# P1R5.net
KiCad netlist of a schematic drawn in EAGLE
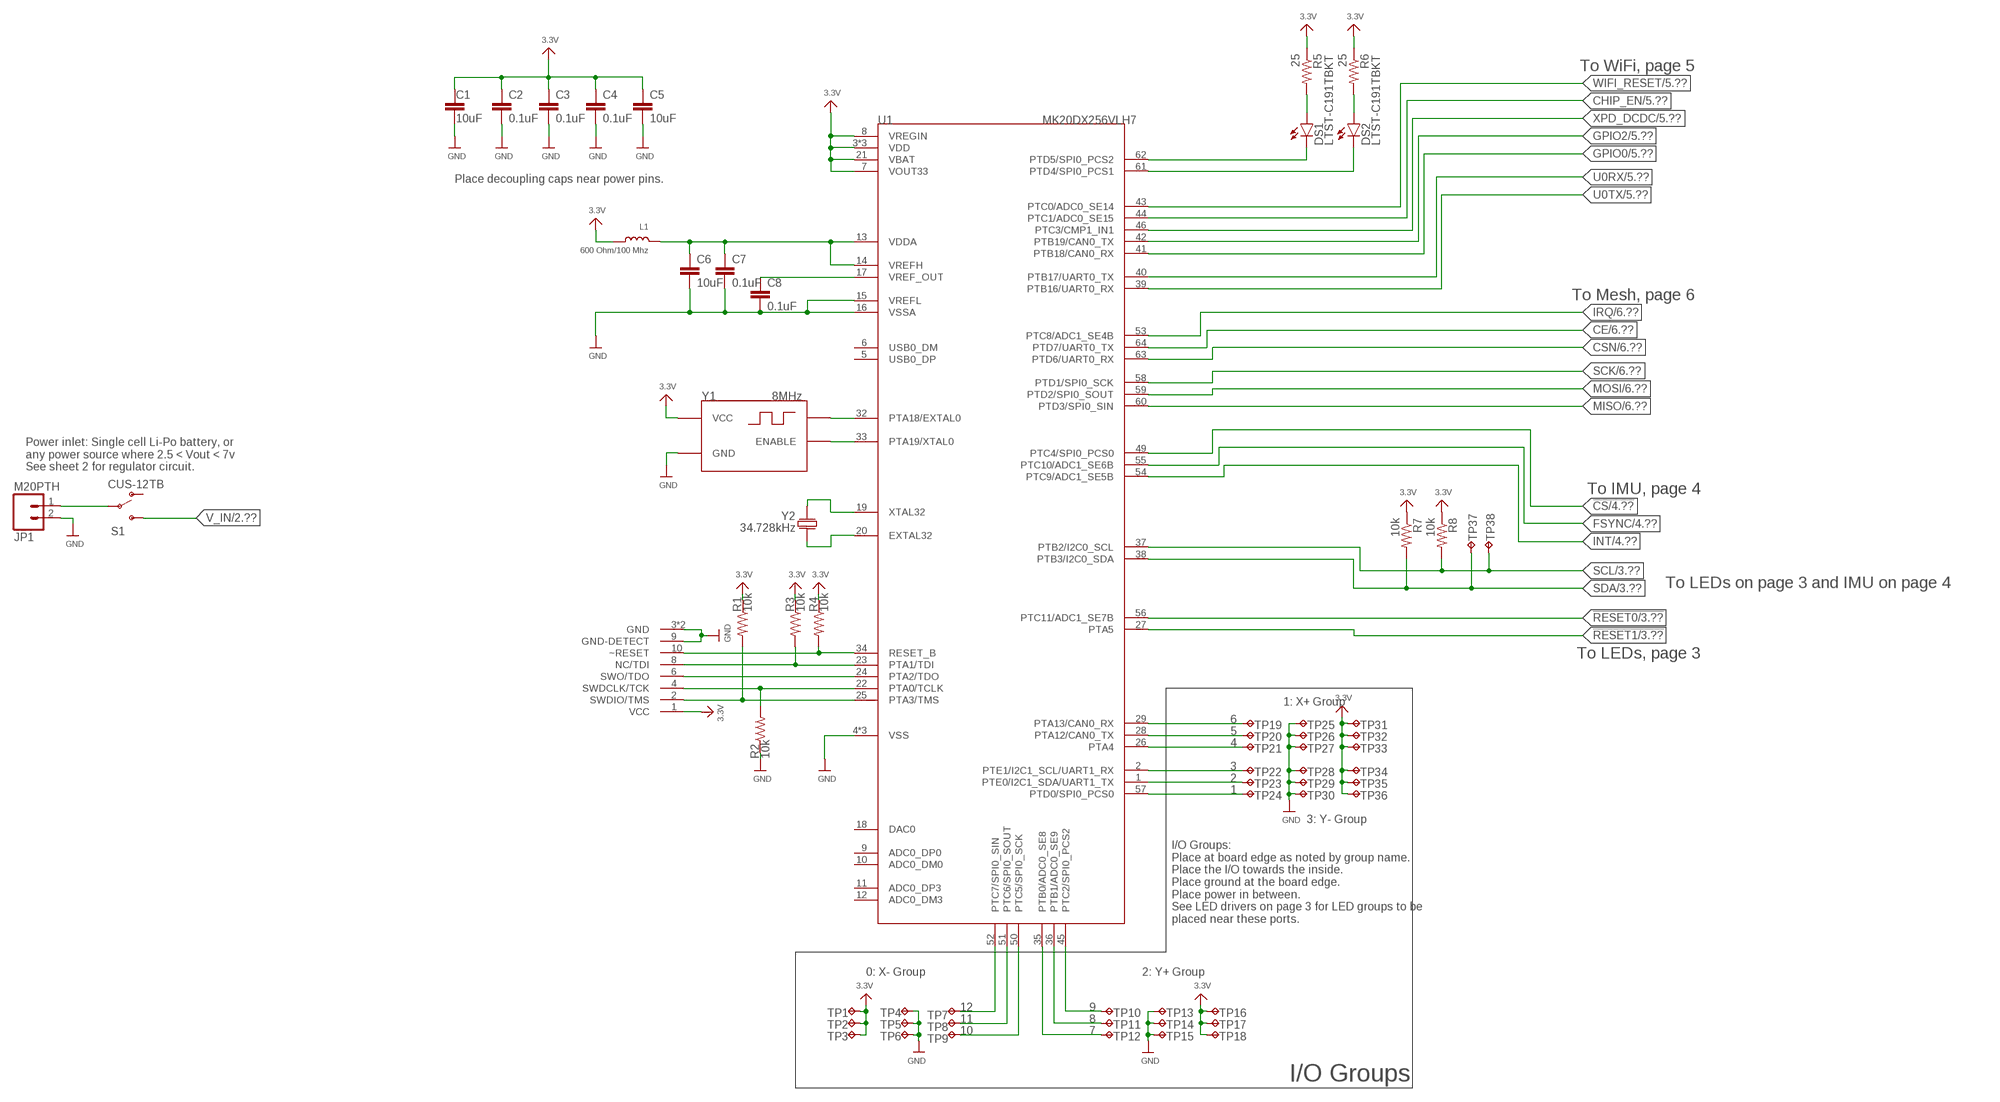
[diagram p0: schematic, sheet 1]
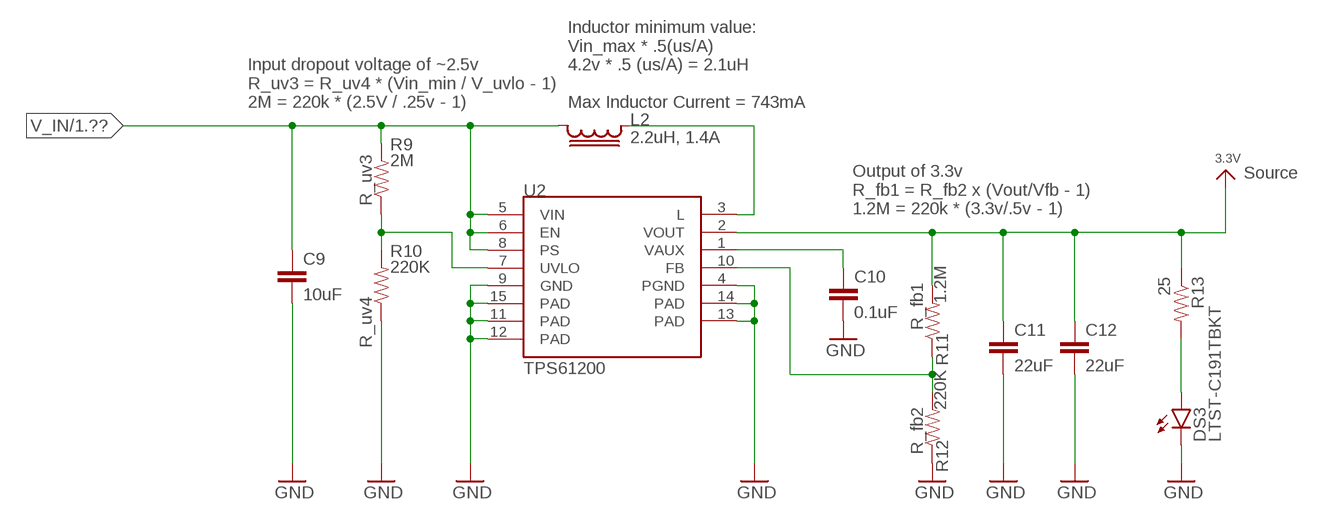
[diagram p1: schematic, sheet 2]
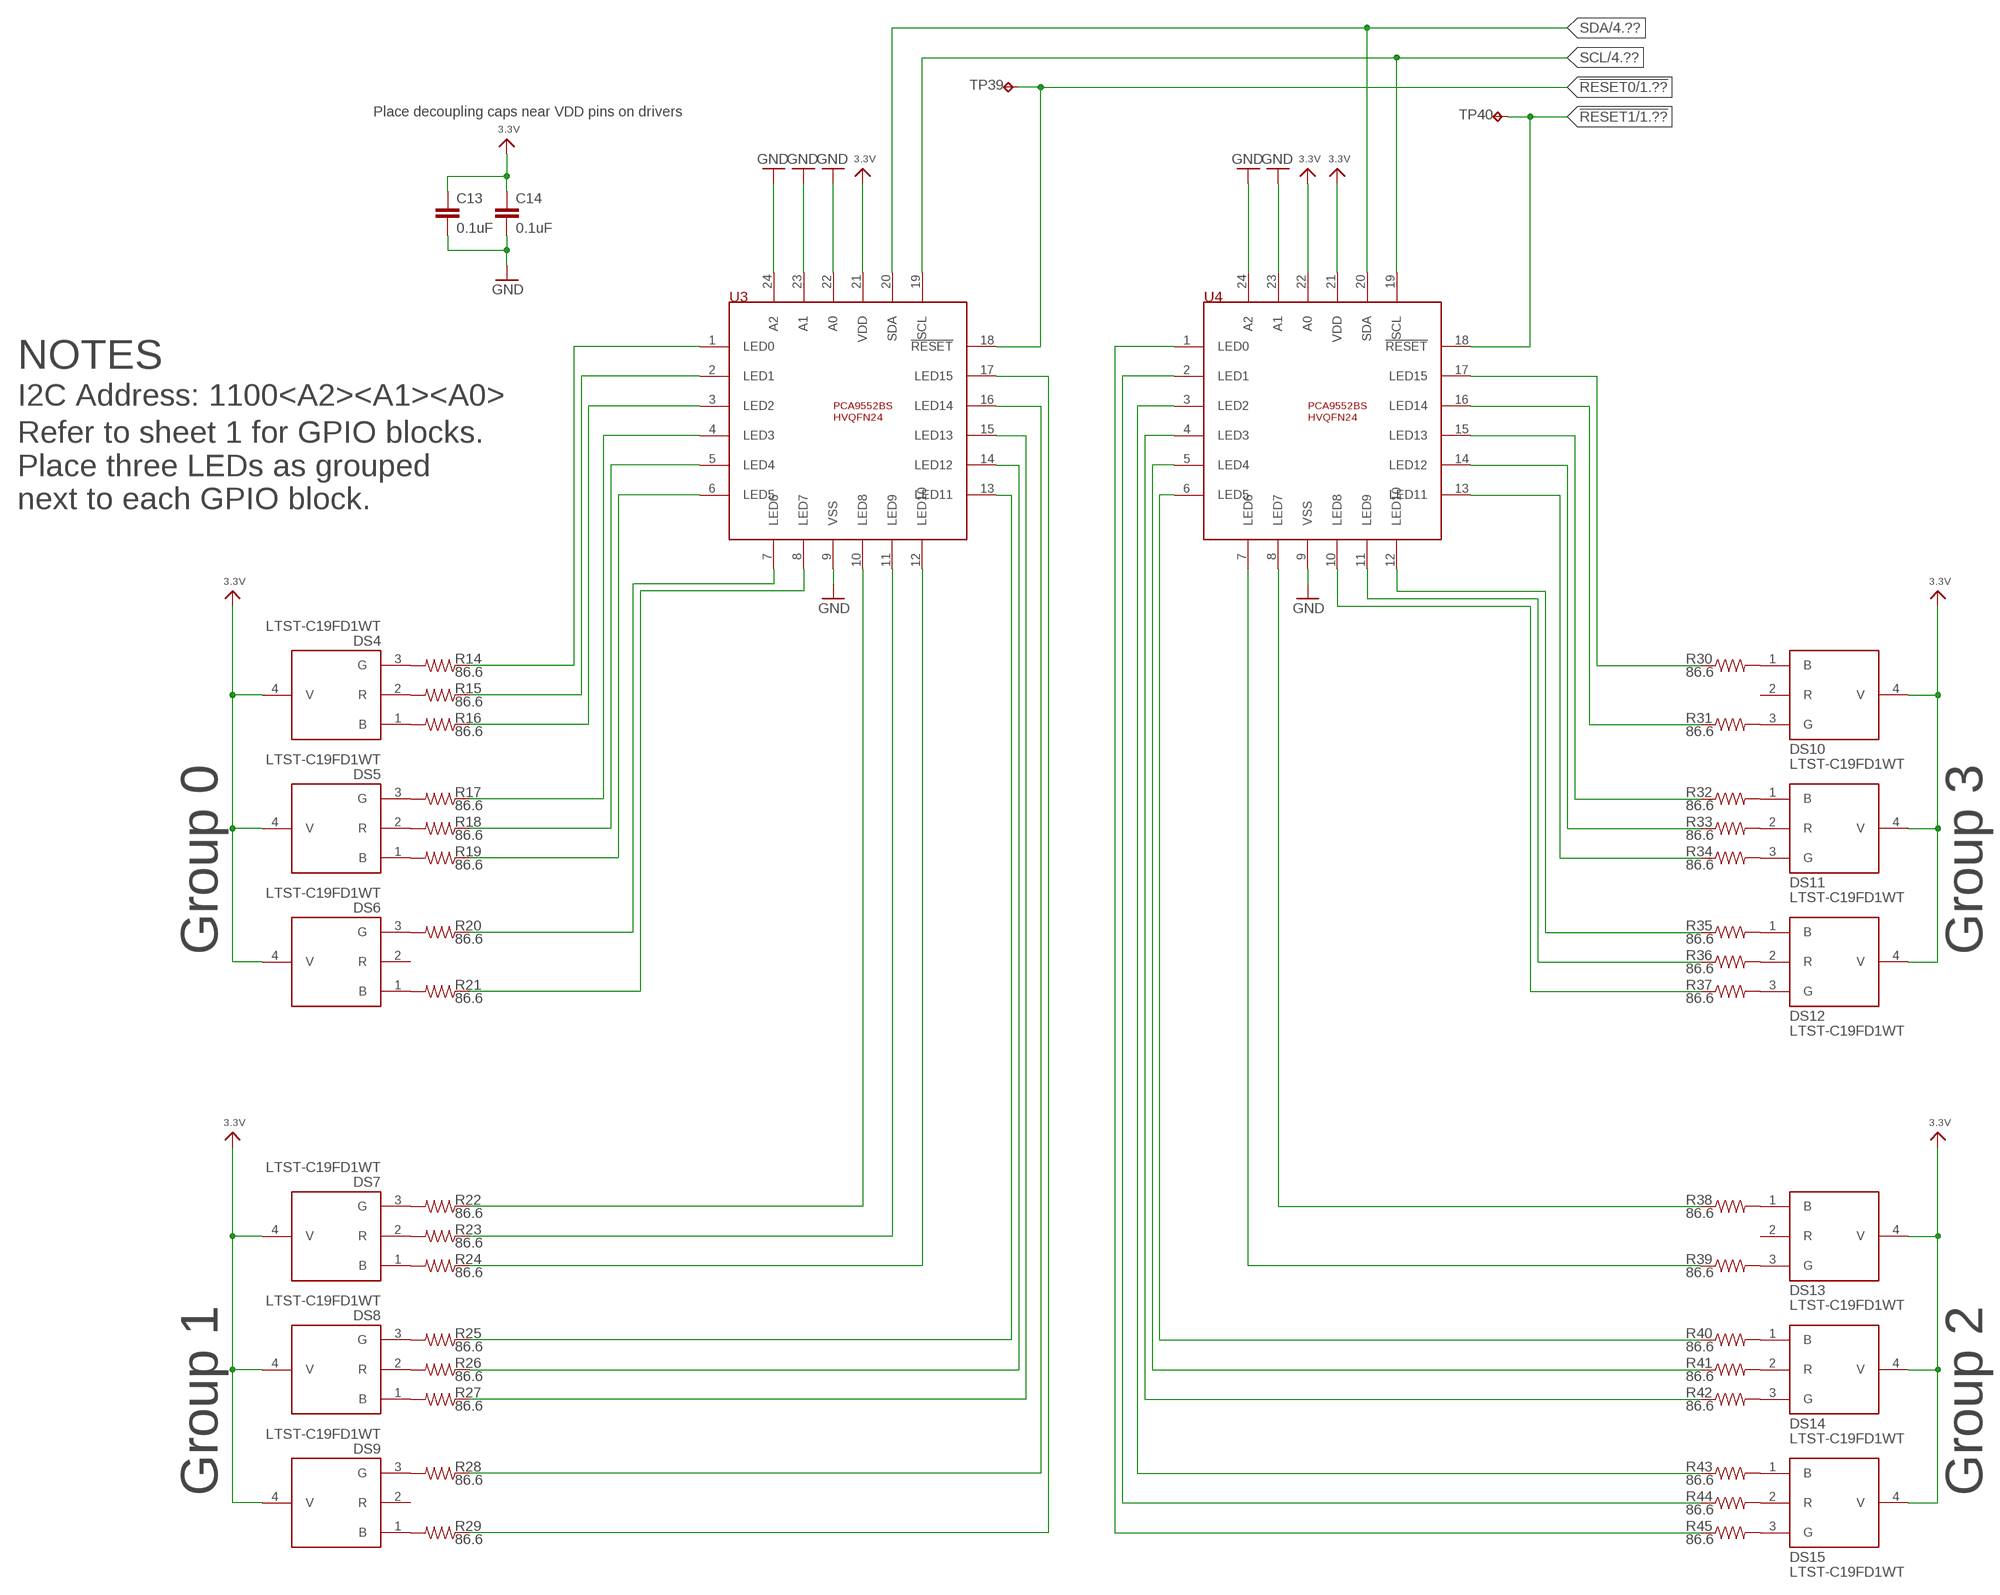
[diagram p2: schematic, sheet 3]
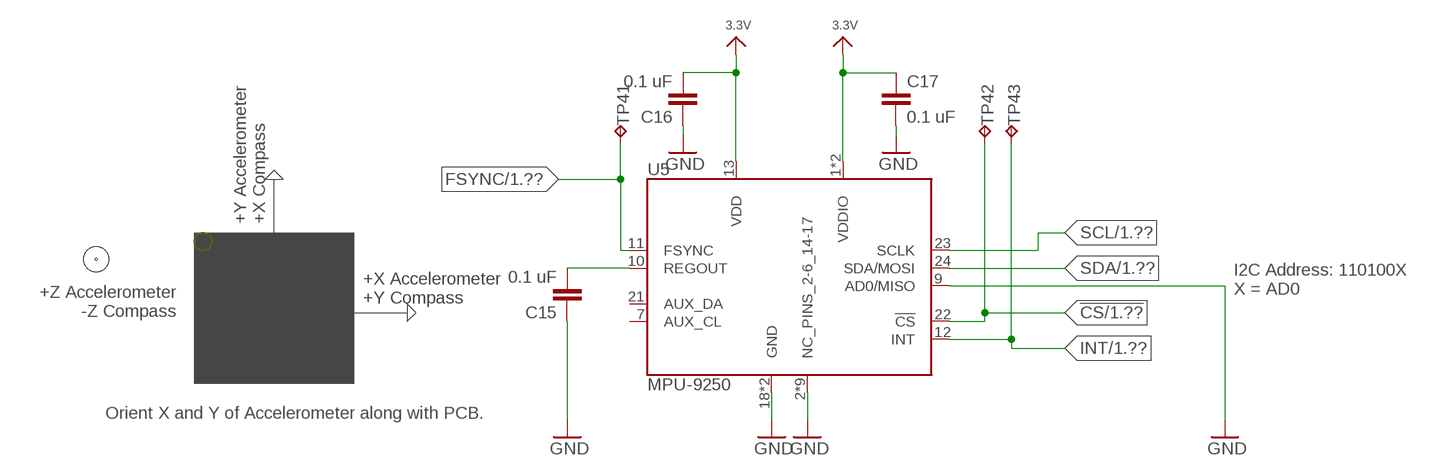
[diagram p3: schematic, sheet 4]
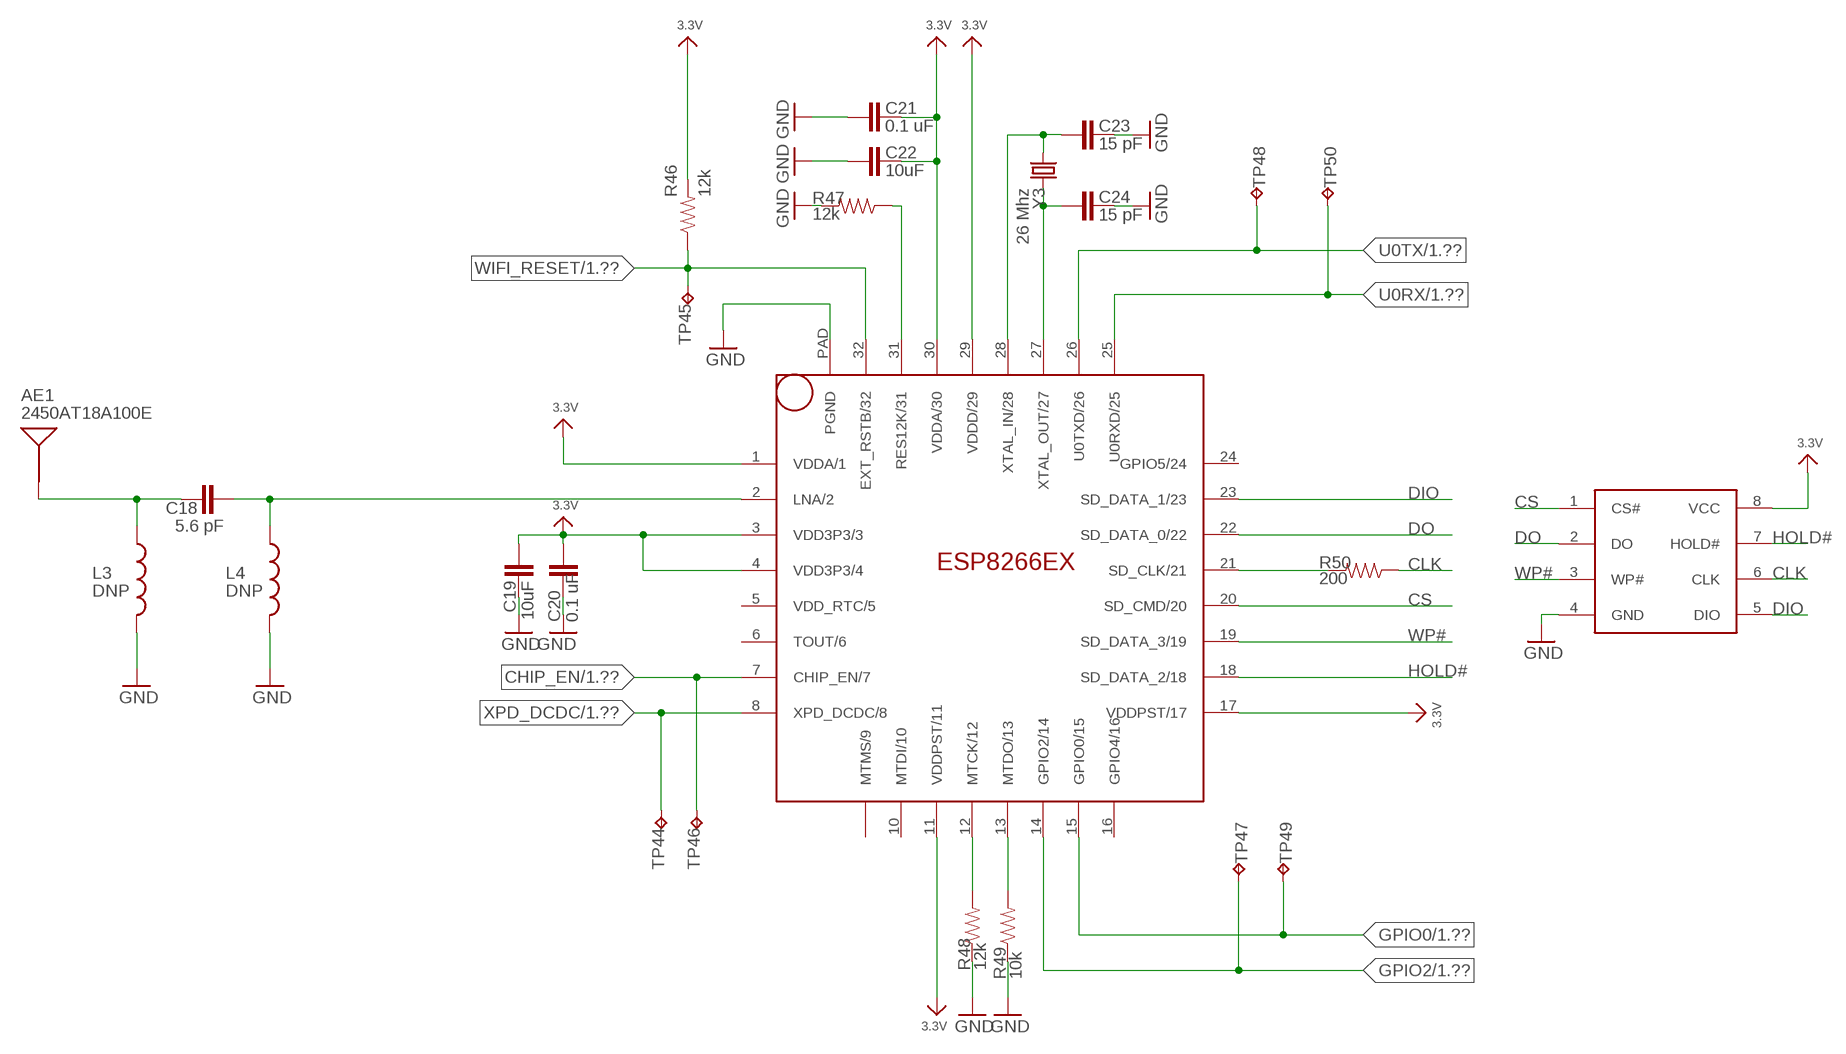
[diagram p4: schematic, sheet 5]
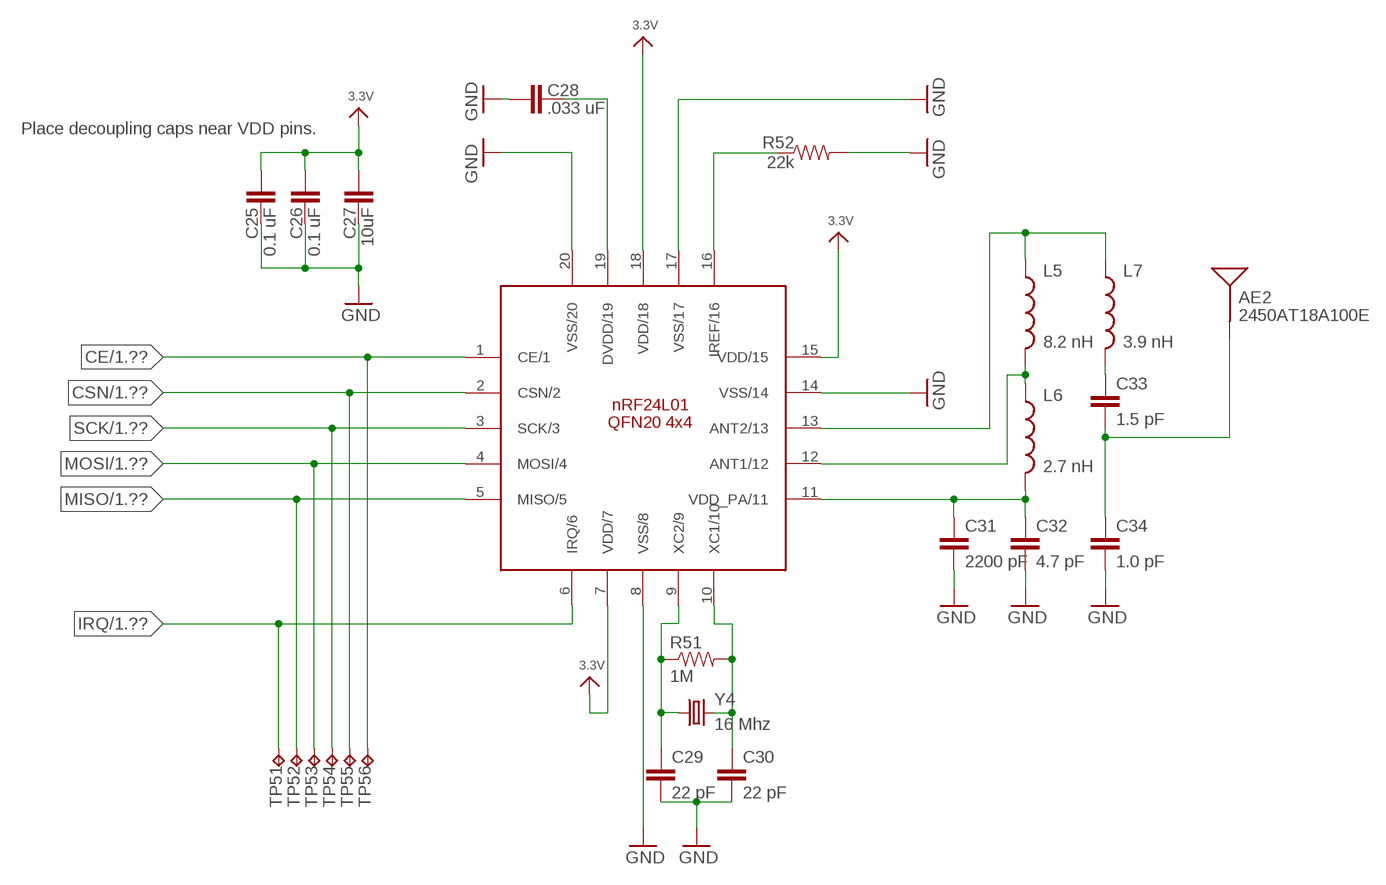
[diagram p5: schematic, sheet 6]

(export (version "E")
  (design (tool "Eeschema 10.0.6"))
  (components
    (comp (ref "C9")
      (value "10uF")
      (footprint "eagle-import:0603-CAP")
      (fields (field (name "PARTNO") "C1608X7S0J106M080AC"))
      (libsource (lib "eagle-import") (part "CAP0603-CAP"))
    )
    (comp (ref "C10")
      (value "0.1uF")
      (footprint "eagle-import:0402-CAP")
      (fields (field (name "PARTNO") "C1005X7R1C104K050BC"))
      (libsource (lib "eagle-import") (part "CAP0402-CAP"))
    )
    (comp (ref "C11")
      (value "22uF")
      (footprint "eagle-import:1210")
      (fields (field (name "PARTNO") "C3225X7R1A226K230AC"))
      (libsource (lib "eagle-import") (part "CAP1210"))
    )
    (comp (ref "C12")
      (value "22uF")
      (footprint "eagle-import:1210")
      (fields (field (name "PARTNO") "C3225X7R1A226K230AC"))
      (libsource (lib "eagle-import") (part "CAP1210"))
    )
    (comp (ref "DS3")
      (value "LTST-C191TBKT")
      (footprint "eagle-import:LED-0603")
      (fields (field (name "MF") "Avago") (field (name "MPN") "HSMG-C190"))
      (libsource (lib "eagle-import") (part "LED-GREEN"))
    )
    (comp (ref "L2")
      (value "2.2uH, 1.4A")
      (footprint "eagle-import:LPS3015")
      (fields
        (field (name "MF") "Coilcraft")
        (field (name "MPN") "LPS3015-222MRB")
        (field (name "PARTNO") "BRL3225T2R2M")
      )
      (libsource (lib "eagle-import") (part "LPS30152.2UH"))
    )
    (comp (ref "R9")
      (value "2M")
      (footprint "eagle-import:_0402")
      (fields (field (name "PARTNO") "CRCW04022M00FKED"))
      (libsource (lib "eagle-import") (part "RESISTOR0402"))
    )
    (comp (ref "R10")
      (value "220K")
      (footprint "eagle-import:_0402")
      (fields (field (name "PARTNO") "CRCW0402220KFKED"))
      (libsource (lib "eagle-import") (part "RESISTOR0402"))
    )
    (comp (ref "R11")
      (value "1.2M")
      (footprint "eagle-import:_0402")
      (fields (field (name "PARTNO") "CRCW04021M20FKED"))
      (libsource (lib "eagle-import") (part "RESISTOR0402"))
    )
    (comp (ref "R12")
      (value "220K")
      (footprint "eagle-import:_0402")
      (fields (field (name "PARTNO") "CRCW0402220KFKED"))
      (libsource (lib "eagle-import") (part "RESISTOR0402"))
    )
    (comp (ref "R13")
      (value "25")
      (footprint "eagle-import:_0402")
      (fields (field (name "PARTNO") "CRCW040224R9FKED"))
      (libsource (lib "eagle-import") (part "RESISTOR0402"))
    )
    (comp (ref "U2")
      (value "TPS61200")
      (footprint "eagle-import:QFN-10_PAD")
      (fields (field (name "MF") "Texas Instruments") (field (name "MPN") "TPS61200DRCR"))
      (libsource (lib "eagle-import") (part "TPS61200"))
    )
    (comp (ref "C13")
      (value "0.1uF")
      (footprint "eagle-import:0402-CAP")
      (fields (field (name "PARTNO") "C1005X7R1C104K050BC"))
      (libsource (lib "eagle-import") (part "CAP0402-CAP"))
    )
    (comp (ref "C14")
      (value "0.1uF")
      (footprint "eagle-import:0402-CAP")
      (fields (field (name "PARTNO") "C1005X7R1C104K050BC"))
      (libsource (lib "eagle-import") (part "CAP0402-CAP"))
    )
    (comp (ref "DS4")
      (value "LTST-C19FD1WT")
      (footprint "eagle-import:LTST-C19FD1WT")
      (libsource (lib "eagle-import") (part "LTST-C19FD1WT"))
    )
    (comp (ref "DS5")
      (value "LTST-C19FD1WT")
      (footprint "eagle-import:LTST-C19FD1WT")
      (libsource (lib "eagle-import") (part "LTST-C19FD1WT"))
    )
    (comp (ref "DS6")
      (value "LTST-C19FD1WT")
      (footprint "eagle-import:LTST-C19FD1WT")
      (libsource (lib "eagle-import") (part "LTST-C19FD1WT"))
    )
    (comp (ref "DS7")
      (value "LTST-C19FD1WT")
      (footprint "eagle-import:LTST-C19FD1WT")
      (libsource (lib "eagle-import") (part "LTST-C19FD1WT"))
    )
    (comp (ref "DS8")
      (value "LTST-C19FD1WT")
      (footprint "eagle-import:LTST-C19FD1WT")
      (libsource (lib "eagle-import") (part "LTST-C19FD1WT"))
    )
    (comp (ref "DS9")
      (value "LTST-C19FD1WT")
      (footprint "eagle-import:LTST-C19FD1WT")
      (libsource (lib "eagle-import") (part "LTST-C19FD1WT"))
    )
    (comp (ref "DS10")
      (value "LTST-C19FD1WT")
      (footprint "eagle-import:LTST-C19FD1WT")
      (libsource (lib "eagle-import") (part "LTST-C19FD1WT"))
    )
    (comp (ref "DS11")
      (value "LTST-C19FD1WT")
      (footprint "eagle-import:LTST-C19FD1WT")
      (libsource (lib "eagle-import") (part "LTST-C19FD1WT"))
    )
    (comp (ref "DS12")
      (value "LTST-C19FD1WT")
      (footprint "eagle-import:LTST-C19FD1WT")
      (libsource (lib "eagle-import") (part "LTST-C19FD1WT"))
    )
    (comp (ref "DS13")
      (value "LTST-C19FD1WT")
      (footprint "eagle-import:LTST-C19FD1WT")
      (libsource (lib "eagle-import") (part "LTST-C19FD1WT"))
    )
    (comp (ref "DS14")
      (value "LTST-C19FD1WT")
      (footprint "eagle-import:LTST-C19FD1WT")
      (libsource (lib "eagle-import") (part "LTST-C19FD1WT"))
    )
    (comp (ref "DS15")
      (value "LTST-C19FD1WT")
      (footprint "eagle-import:LTST-C19FD1WT")
      (libsource (lib "eagle-import") (part "LTST-C19FD1WT"))
    )
    (comp (ref "R14")
      (value "86.6")
      (footprint "eagle-import:_0402")
      (fields (field (name "PARTNO") "5-1879213-0"))
      (libsource (lib "eagle-import") (part "RESISTOR0402"))
    )
    (comp (ref "R15")
      (value "86.6")
      (footprint "eagle-import:_0402")
      (fields (field (name "PARTNO") "5-1879213-0"))
      (libsource (lib "eagle-import") (part "RESISTOR0402"))
    )
    (comp (ref "R16")
      (value "86.6")
      (footprint "eagle-import:_0402")
      (fields (field (name "PARTNO") "5-1879213-0"))
      (libsource (lib "eagle-import") (part "RESISTOR0402"))
    )
    (comp (ref "R17")
      (value "86.6")
      (footprint "eagle-import:_0402")
      (fields (field (name "PARTNO") "5-1879213-0"))
      (libsource (lib "eagle-import") (part "RESISTOR0402"))
    )
    (comp (ref "R18")
      (value "86.6")
      (footprint "eagle-import:_0402")
      (fields (field (name "PARTNO") "5-1879213-0"))
      (libsource (lib "eagle-import") (part "RESISTOR0402"))
    )
    (comp (ref "R19")
      (value "86.6")
      (footprint "eagle-import:_0402")
      (fields (field (name "PARTNO") "5-1879213-0"))
      (libsource (lib "eagle-import") (part "RESISTOR0402"))
    )
    (comp (ref "R20")
      (value "86.6")
      (footprint "eagle-import:_0402")
      (fields (field (name "PARTNO") "5-1879213-0"))
      (libsource (lib "eagle-import") (part "RESISTOR0402"))
    )
    (comp (ref "R21")
      (value "86.6")
      (footprint "eagle-import:_0402")
      (fields (field (name "PARTNO") "5-1879213-0"))
      (libsource (lib "eagle-import") (part "RESISTOR0402"))
    )
    (comp (ref "R22")
      (value "86.6")
      (footprint "eagle-import:_0402")
      (fields (field (name "PARTNO") "5-1879213-0"))
      (libsource (lib "eagle-import") (part "RESISTOR0402"))
    )
    (comp (ref "R23")
      (value "86.6")
      (footprint "eagle-import:_0402")
      (fields (field (name "PARTNO") "5-1879213-0"))
      (libsource (lib "eagle-import") (part "RESISTOR0402"))
    )
    (comp (ref "R24")
      (value "86.6")
      (footprint "eagle-import:_0402")
      (fields (field (name "PARTNO") "5-1879213-0"))
      (libsource (lib "eagle-import") (part "RESISTOR0402"))
    )
    (comp (ref "R25")
      (value "86.6")
      (footprint "eagle-import:_0402")
      (fields (field (name "PARTNO") "5-1879213-0"))
      (libsource (lib "eagle-import") (part "RESISTOR0402"))
    )
    (comp (ref "R26")
      (value "86.6")
      (footprint "eagle-import:_0402")
      (fields (field (name "PARTNO") "5-1879213-0"))
      (libsource (lib "eagle-import") (part "RESISTOR0402"))
    )
    (comp (ref "R27")
      (value "86.6")
      (footprint "eagle-import:_0402")
      (fields (field (name "PARTNO") "5-1879213-0"))
      (libsource (lib "eagle-import") (part "RESISTOR0402"))
    )
    (comp (ref "R28")
      (value "86.6")
      (footprint "eagle-import:_0402")
      (fields (field (name "PARTNO") "5-1879213-0"))
      (libsource (lib "eagle-import") (part "RESISTOR0402"))
    )
    (comp (ref "R29")
      (value "86.6")
      (footprint "eagle-import:_0402")
      (fields (field (name "PARTNO") "5-1879213-0"))
      (libsource (lib "eagle-import") (part "RESISTOR0402"))
    )
    (comp (ref "R30")
      (value "86.6")
      (footprint "eagle-import:_0402")
      (fields (field (name "PARTNO") "5-1879213-0"))
      (libsource (lib "eagle-import") (part "RESISTOR0402"))
    )
    (comp (ref "R31")
      (value "86.6")
      (footprint "eagle-import:_0402")
      (fields (field (name "PARTNO") "5-1879213-0"))
      (libsource (lib "eagle-import") (part "RESISTOR0402"))
    )
    (comp (ref "R32")
      (value "86.6")
      (footprint "eagle-import:_0402")
      (fields (field (name "PARTNO") "5-1879213-0"))
      (libsource (lib "eagle-import") (part "RESISTOR0402"))
    )
    (comp (ref "R33")
      (value "86.6")
      (footprint "eagle-import:_0402")
      (fields (field (name "PARTNO") "5-1879213-0"))
      (libsource (lib "eagle-import") (part "RESISTOR0402"))
    )
    (comp (ref "R34")
      (value "86.6")
      (footprint "eagle-import:_0402")
      (fields (field (name "PARTNO") "5-1879213-0"))
      (libsource (lib "eagle-import") (part "RESISTOR0402"))
    )
    (comp (ref "R35")
      (value "86.6")
      (footprint "eagle-import:_0402")
      (fields (field (name "PARTNO") "5-1879213-0"))
      (libsource (lib "eagle-import") (part "RESISTOR0402"))
    )
    (comp (ref "R36")
      (value "86.6")
      (footprint "eagle-import:_0402")
      (fields (field (name "PARTNO") "5-1879213-0"))
      (libsource (lib "eagle-import") (part "RESISTOR0402"))
    )
    (comp (ref "R37")
      (value "86.6")
      (footprint "eagle-import:_0402")
      (fields (field (name "PARTNO") "5-1879213-0"))
      (libsource (lib "eagle-import") (part "RESISTOR0402"))
    )
    (comp (ref "R38")
      (value "86.6")
      (footprint "eagle-import:_0402")
      (fields (field (name "PARTNO") "5-1879213-0"))
      (libsource (lib "eagle-import") (part "RESISTOR0402"))
    )
    (comp (ref "R39")
      (value "86.6")
      (footprint "eagle-import:_0402")
      (fields (field (name "PARTNO") "5-1879213-0"))
      (libsource (lib "eagle-import") (part "RESISTOR0402"))
    )
    (comp (ref "R40")
      (value "86.6")
      (footprint "eagle-import:_0402")
      (fields (field (name "PARTNO") "5-1879213-0"))
      (libsource (lib "eagle-import") (part "RESISTOR0402"))
    )
    (comp (ref "R41")
      (value "86.6")
      (footprint "eagle-import:_0402")
      (fields (field (name "PARTNO") "5-1879213-0"))
      (libsource (lib "eagle-import") (part "RESISTOR0402"))
    )
    (comp (ref "R42")
      (value "86.6")
      (footprint "eagle-import:_0402")
      (fields (field (name "PARTNO") "5-1879213-0"))
      (libsource (lib "eagle-import") (part "RESISTOR0402"))
    )
    (comp (ref "R43")
      (value "86.6")
      (footprint "eagle-import:_0402")
      (fields (field (name "PARTNO") "5-1879213-0"))
      (libsource (lib "eagle-import") (part "RESISTOR0402"))
    )
    (comp (ref "R44")
      (value "86.6")
      (footprint "eagle-import:_0402")
      (fields (field (name "PARTNO") "5-1879213-0"))
      (libsource (lib "eagle-import") (part "RESISTOR0402"))
    )
    (comp (ref "R45")
      (value "86.6")
      (footprint "eagle-import:_0402")
      (fields (field (name "PARTNO") "5-1879213-0"))
      (libsource (lib "eagle-import") (part "RESISTOR0402"))
    )
    (comp (ref "TP39")
      (value "TPTP08R")
      (footprint "eagle-import:TP08R")
      (fields (field (name "PARTNO") "TEST POINT"))
      (libsource (lib "eagle-import") (part "TPTP08R"))
    )
    (comp (ref "TP40")
      (value "TPTP08R")
      (footprint "eagle-import:TP08R")
      (fields (field (name "PARTNO") "TEST POINT"))
      (libsource (lib "eagle-import") (part "TPTP08R"))
    )
    (comp (ref "U3")
      (value "PCA9552BS")
      (footprint "eagle-import:HVQFN24")
      (libsource (lib "eagle-import") (part "PCA9552BS"))
    )
    (comp (ref "U4")
      (value "PCA9552BS")
      (footprint "eagle-import:HVQFN24")
      (libsource (lib "eagle-import") (part "PCA9552BS"))
    )
    (comp (ref "AE2")
      (value "2450AT18A100E")
      (footprint "eagle-import:ANTENNA-CHIP2")
      (libsource (lib "eagle-import") (part "ANTENNA2SMD"))
    )
    (comp (ref "C25")
      (value "0.1 uF")
      (footprint "eagle-import:0402-CAP")
      (fields (field (name "PARTNO") "C1005X7R1C104K050BC"))
      (libsource (lib "eagle-import") (part "CAP0402-CAP"))
    )
    (comp (ref "C26")
      (value "0.1 uF")
      (footprint "eagle-import:0402-CAP")
      (fields (field (name "PARTNO") "C1005X7R1C104K050BC"))
      (libsource (lib "eagle-import") (part "CAP0402-CAP"))
    )
    (comp (ref "C27")
      (value "10uF")
      (footprint "eagle-import:0603-CAP")
      (fields (field (name "PARTNO") "C1608X7S0J106M080AC"))
      (libsource (lib "eagle-import") (part "CAP0603-CAP"))
    )
    (comp (ref "C28")
      (value ".033 uF")
      (footprint "eagle-import:0402-CAP")
      (fields (field (name "PARTNO") "C1005X7R1H333K050BB"))
      (libsource (lib "eagle-import") (part "CAP0402-CAP"))
    )
    (comp (ref "C29")
      (value "22 pF")
      (footprint "eagle-import:0402-CAP")
      (fields (field (name "PARTNO") "C1005C0G1H220J050BA"))
      (libsource (lib "eagle-import") (part "CAP0402-CAP"))
    )
    (comp (ref "C30")
      (value "22 pF")
      (footprint "eagle-import:0402-CAP")
      (fields (field (name "PARTNO") "C1005C0G1H220J050BA"))
      (libsource (lib "eagle-import") (part "CAP0402-CAP"))
    )
    (comp (ref "C31")
      (value "2200 pF")
      (footprint "eagle-import:0402-CAP")
      (fields (field (name "PARTNO") "C1005X7R1H222K050BA"))
      (libsource (lib "eagle-import") (part "CAP0402-CAP"))
    )
    (comp (ref "C32")
      (value "4.7 pF")
      (footprint "eagle-import:0402-CAP")
      (fields (field (name "PARTNO") "CGA2B2C0G1H4R7C050BA"))
      (libsource (lib "eagle-import") (part "CAP0402-CAP"))
    )
    (comp (ref "C33")
      (value "1.5 pF")
      (footprint "eagle-import:0402-CAP")
      (fields (field (name "PARTNO") "C1005C0G1H1R5B050BA"))
      (libsource (lib "eagle-import") (part "CAP0402-CAP"))
    )
    (comp (ref "C34")
      (value "1.0 pF")
      (footprint "eagle-import:0402-CAP")
      (fields (field (name "PARTNO") "C1005C0G1H010B050BA"))
      (libsource (lib "eagle-import") (part "CAP0402-CAP"))
    )
    (comp (ref "L5")
      (value "8.2 nH")
      (footprint "eagle-import:C0402")
      (fields (field (name "PARTNO") "L-07C8N2JV6T"))
      (libsource (lib "eagle-import") (part "INDUCTOR0402"))
    )
    (comp (ref "L6")
      (value "2.7 nH")
      (footprint "eagle-import:C0402")
      (fields (field (name "PARTNO") "L-07C2N7SV6T"))
      (libsource (lib "eagle-import") (part "INDUCTOR0402"))
    )
    (comp (ref "L7")
      (value "3.9 nH")
      (footprint "eagle-import:C0402")
      (fields (field (name "PARTNO") "L-07C3N9SV6T"))
      (libsource (lib "eagle-import") (part "INDUCTOR0402"))
    )
    (comp (ref "R51")
      (value "1M")
      (footprint "eagle-import:_0402")
      (fields (field (name "PARTNO") "CRCW04021M00FKED"))
      (libsource (lib "eagle-import") (part "RESISTOR0402"))
    )
    (comp (ref "R52")
      (value "22k")
      (footprint "eagle-import:_0402")
      (fields (field (name "PARTNO") "CRCW040222K0FKED"))
      (libsource (lib "eagle-import") (part "RESISTOR0402"))
    )
    (comp (ref "TP51")
      (value "TPTP08R")
      (footprint "eagle-import:TP08R")
      (fields (field (name "PARTNO") "TEST POINT"))
      (libsource (lib "eagle-import") (part "TPTP08R"))
    )
    (comp (ref "TP52")
      (value "TPTP08R")
      (footprint "eagle-import:TP08R")
      (fields (field (name "PARTNO") "TEST POINT"))
      (libsource (lib "eagle-import") (part "TPTP08R"))
    )
    (comp (ref "TP53")
      (value "TPTP08R")
      (footprint "eagle-import:TP08R")
      (fields (field (name "PARTNO") "TEST POINT"))
      (libsource (lib "eagle-import") (part "TPTP08R"))
    )
    (comp (ref "TP54")
      (value "TPTP08R")
      (footprint "eagle-import:TP08R")
      (fields (field (name "PARTNO") "TEST POINT"))
      (libsource (lib "eagle-import") (part "TPTP08R"))
    )
    (comp (ref "TP55")
      (value "TPTP08R")
      (footprint "eagle-import:TP08R")
      (fields (field (name "PARTNO") "TEST POINT"))
      (libsource (lib "eagle-import") (part "TPTP08R"))
    )
    (comp (ref "TP56")
      (value "TPTP08R")
      (footprint "eagle-import:TP08R")
      (fields (field (name "PARTNO") "TEST POINT"))
      (libsource (lib "eagle-import") (part "TPTP08R"))
    )
    (comp (ref "U8")
      (value "NRF24L01")
      (footprint "eagle-import:QFN20(4X4)")
      (fields (field (name "PARTNO") "NRF24L01P-T"))
      (libsource (lib "eagle-import") (part "NRF24L01"))
    )
    (comp (ref "Y4")
      (value "16 Mhz")
      (footprint "eagle-import:CRYSTAL-SMD-5X3")
      (fields (field (name "PARTNO") "7B-16.000MAAJ-T"))
      (libsource (lib "eagle-import") (part "CRYSTAL5X3"))
    )
    (comp (ref "AE1")
      (value "2450AT18A100E")
      (footprint "eagle-import:ANTENNA-CHIP2")
      (libsource (lib "eagle-import") (part "ANTENNA2SMD"))
    )
    (comp (ref "C18")
      (value "5.6 pF")
      (footprint "eagle-import:0402-CAP")
      (fields (field (name "PARTNO") "GRM1555C1H5R6CA01D"))
      (libsource (lib "eagle-import") (part "CAP0402-CAP"))
    )
    (comp (ref "C19")
      (value "10uF")
      (footprint "eagle-import:0603-CAP")
      (fields (field (name "PARTNO") "C1608X7S0J106M080AC"))
      (libsource (lib "eagle-import") (part "CAP0603-CAP"))
    )
    (comp (ref "C20")
      (value "0.1 uF")
      (footprint "eagle-import:0402-CAP")
      (fields (field (name "PARTNO") "C1005X7R1C104K050BC"))
      (libsource (lib "eagle-import") (part "CAP0402-CAP"))
    )
    (comp (ref "C21")
      (value "0.1 uF")
      (footprint "eagle-import:0402-CAP")
      (fields (field (name "PARTNO") "C1005X7R1C104K050BC"))
      (libsource (lib "eagle-import") (part "CAP0402-CAP"))
    )
    (comp (ref "C22")
      (value "10uF")
      (footprint "eagle-import:0603-CAP")
      (fields (field (name "PARTNO") "C1608X7S0J106M080AC"))
      (libsource (lib "eagle-import") (part "CAP0603-CAP"))
    )
    (comp (ref "C23")
      (value "15 pF")
      (footprint "eagle-import:0402-CAP")
      (fields (field (name "PARTNO") "C1005C0G1H150J050BA"))
      (libsource (lib "eagle-import") (part "CAP0402-CAP"))
    )
    (comp (ref "C24")
      (value "15 pF")
      (footprint "eagle-import:0402-CAP")
      (fields (field (name "PARTNO") "C1005C0G1H150J050BA"))
      (libsource (lib "eagle-import") (part "CAP0402-CAP"))
    )
    (comp (ref "L3")
      (value "DNP")
      (footprint "eagle-import:0603")
      (libsource (lib "eagle-import") (part "INDUCTOR30OHM,1.8A"))
    )
    (comp (ref "L4")
      (value "DNP")
      (footprint "eagle-import:0603")
      (libsource (lib "eagle-import") (part "INDUCTOR30OHM,1.8A"))
    )
    (comp (ref "R46")
      (value "12k")
      (footprint "eagle-import:_0402")
      (fields (field (name "PARTNO") "CRCW040212K0FKED"))
      (libsource (lib "eagle-import") (part "RESISTOR0402"))
    )
    (comp (ref "R47")
      (value "12k")
      (footprint "eagle-import:_0402")
      (fields (field (name "PARTNO") "CRCW040212K0FKED"))
      (libsource (lib "eagle-import") (part "RESISTOR0402"))
    )
    (comp (ref "R48")
      (value "12k")
      (footprint "eagle-import:_0402")
      (fields (field (name "PARTNO") "CRCW040212K0FKED"))
      (libsource (lib "eagle-import") (part "RESISTOR0402"))
    )
    (comp (ref "R49")
      (value "10k")
      (footprint "eagle-import:_0402")
      (fields (field (name "PARTNO") "CRCW040210K0FKED"))
      (libsource (lib "eagle-import") (part "RESISTOR0402"))
    )
    (comp (ref "R50")
      (value "200")
      (footprint "eagle-import:_0402")
      (fields (field (name "PARTNO") "CRCW0402200RFKED"))
      (libsource (lib "eagle-import") (part "RESISTOR0402"))
    )
    (comp (ref "TP44")
      (value "TPTP08R")
      (footprint "eagle-import:TP08R")
      (fields (field (name "PARTNO") "TEST POINT"))
      (libsource (lib "eagle-import") (part "TPTP08R"))
    )
    (comp (ref "TP45")
      (value "TPTP08R")
      (footprint "eagle-import:TP08R")
      (fields (field (name "PARTNO") "TEST POINT"))
      (libsource (lib "eagle-import") (part "TPTP08R"))
    )
    (comp (ref "TP46")
      (value "TPTP08R")
      (footprint "eagle-import:TP08R")
      (fields (field (name "PARTNO") "TEST POINT"))
      (libsource (lib "eagle-import") (part "TPTP08R"))
    )
    (comp (ref "TP47")
      (value "TPTP08R")
      (footprint "eagle-import:TP08R")
      (fields (field (name "PARTNO") "TEST POINT"))
      (libsource (lib "eagle-import") (part "TPTP08R"))
    )
    (comp (ref "TP48")
      (value "TPTP08R")
      (footprint "eagle-import:TP08R")
      (fields (field (name "PARTNO") "TEST POINT"))
      (libsource (lib "eagle-import") (part "TPTP08R"))
    )
    (comp (ref "TP49")
      (value "TPTP08R")
      (footprint "eagle-import:TP08R")
      (fields (field (name "PARTNO") "TEST POINT"))
      (libsource (lib "eagle-import") (part "TPTP08R"))
    )
    (comp (ref "TP50")
      (value "TPTP08R")
      (footprint "eagle-import:TP08R")
      (fields (field (name "PARTNO") "TEST POINT"))
      (libsource (lib "eagle-import") (part "TPTP08R"))
    )
    (comp (ref "U6")
      (value "ESP8266EX")
      (footprint "eagle-import:QFN32")
      (libsource (lib "eagle-import") (part "ESP8266EX"))
    )
    (comp (ref "U7")
      (value "25Q40")
      (footprint "eagle-import:SOP8")
      (libsource (lib "eagle-import") (part "25Q40"))
    )
    (comp (ref "Y3")
      (value "26 Mhz")
      (footprint "eagle-import:CRYSTAL-SMD-5X3")
      (fields (field (name "PARTNO") "7M-26.000MAAJ-T"))
      (libsource (lib "eagle-import") (part "CRYSTAL5X3"))
    )
    (comp (ref "C15")
      (value "0.1 uF")
      (footprint "eagle-import:0402-CAP")
      (fields (field (name "PARTNO") "C1005X7R1C104K050BC"))
      (libsource (lib "eagle-import") (part "CAP0402-CAP"))
    )
    (comp (ref "C16")
      (value "0.1 uF")
      (footprint "eagle-import:0402-CAP")
      (fields (field (name "PARTNO") "C1005X7R1C104K050BC"))
      (libsource (lib "eagle-import") (part "CAP0402-CAP"))
    )
    (comp (ref "C17")
      (value "0.1 uF")
      (footprint "eagle-import:0402-CAP")
      (fields (field (name "PARTNO") "C1005X7R1C104K050BC"))
      (libsource (lib "eagle-import") (part "CAP0402-CAP"))
    )
    (comp (ref "TP41")
      (value "TPTP08R")
      (footprint "eagle-import:TP08R")
      (fields (field (name "PARTNO") "TEST POINT"))
      (libsource (lib "eagle-import") (part "TPTP08R"))
    )
    (comp (ref "TP42")
      (value "TPTP08R")
      (footprint "eagle-import:TP08R")
      (fields (field (name "PARTNO") "TEST POINT"))
      (libsource (lib "eagle-import") (part "TPTP08R"))
    )
    (comp (ref "TP43")
      (value "TPTP08R")
      (footprint "eagle-import:TP08R")
      (fields (field (name "PARTNO") "TEST POINT"))
      (libsource (lib "eagle-import") (part "TPTP08R"))
    )
    (comp (ref "U5")
      (value "MPU-9250")
      (footprint "eagle-import:QFN-24_3MM")
      (libsource (lib "eagle-import") (part "MPU-9250"))
    )
    (comp (ref "C1")
      (value "10uF")
      (footprint "eagle-import:0603-CAP")
      (fields (field (name "PARTNO") "C1608X7S0J106M080AC"))
      (libsource (lib "eagle-import") (part "CAP0603-CAP"))
    )
    (comp (ref "C2")
      (value "0.1uF")
      (footprint "eagle-import:0402-CAP")
      (fields (field (name "PARTNO") "C1005X7R1C104K050BC"))
      (libsource (lib "eagle-import") (part "CAP0402-CAP"))
    )
    (comp (ref "C3")
      (value "0.1uF")
      (footprint "eagle-import:0402-CAP")
      (fields (field (name "PARTNO") "C1005X7R1C104K050BC"))
      (libsource (lib "eagle-import") (part "CAP0402-CAP"))
    )
    (comp (ref "C4")
      (value "0.1uF")
      (footprint "eagle-import:0402-CAP")
      (fields (field (name "PARTNO") "C1005X7R1C104K050BC"))
      (libsource (lib "eagle-import") (part "CAP0402-CAP"))
    )
    (comp (ref "C5")
      (value "10uF")
      (footprint "eagle-import:0603-CAP")
      (fields (field (name "PARTNO") "C1608X7S0J106M080AC"))
      (libsource (lib "eagle-import") (part "CAP0603-CAP"))
    )
    (comp (ref "C6")
      (value "10uF")
      (footprint "eagle-import:0603-CAP")
      (fields (field (name "PARTNO") "C1608X7S0J106M080AC"))
      (libsource (lib "eagle-import") (part "CAP0603-CAP"))
    )
    (comp (ref "C7")
      (value "0.1uF")
      (footprint "eagle-import:0402-CAP")
      (fields (field (name "PARTNO") "C1005X7R1C104K050BC"))
      (libsource (lib "eagle-import") (part "CAP0402-CAP"))
    )
    (comp (ref "C8")
      (value "0.1uF")
      (footprint "eagle-import:0402-CAP")
      (fields (field (name "PARTNO") "C1005X7R1C104K050BC"))
      (libsource (lib "eagle-import") (part "CAP0402-CAP"))
    )
    (comp (ref "DS1")
      (value "LTST-C191TBKT")
      (footprint "eagle-import:LED-0603")
      (fields (field (name "MF") "Avago") (field (name "MPN") "HSMG-C190"))
      (libsource (lib "eagle-import") (part "LED-GREEN"))
    )
    (comp (ref "DS2")
      (value "LTST-C191TBKT")
      (footprint "eagle-import:LED-0603")
      (fields (field (name "MF") "Avago") (field (name "MPN") "HSMG-C190"))
      (libsource (lib "eagle-import") (part "LED-GREEN"))
    )
    (comp (ref "J1")
      (value "2X5_0.05\"_CORTEX_DEBUGTH_NOKEY_UNSHROUDED")
      (footprint "eagle-import:2X5_0.05__TH_NS")
      (fields (field (name "PARTNO") "20021111-00010T4LF"))
      (libsource (lib "eagle-import") (part "2X5_0.05{dblquote}_CORTEX_DEBUGTH_NOKEY_UNSHROUDED"))
    )
    (comp (ref "JP1")
      (value "M20PTH")
      (footprint "eagle-import:JST_2PIN")
      (fields (field (name "PARTNO") "S2B-PH-K-S(LF)(SN)"))
      (libsource (lib "eagle-import") (part "M02PTH"))
    )
    (comp (ref "L1")
      (value "600 Ohm/100 Mhz")
      (footprint "eagle-import:0805")
      (fields (field (name "MF") "Taiyo Yuden") (field (name "MPN") "BK2125HM601-T"))
      (libsource (lib "eagle-import") (part "INDUCTOR-BK2125HM601-T"))
    )
    (comp (ref "R1")
      (value "10k")
      (footprint "eagle-import:_0402")
      (fields (field (name "PARTNO") "CRCW040210K0FKED"))
      (libsource (lib "eagle-import") (part "RESISTOR0402"))
    )
    (comp (ref "R2")
      (value "10k")
      (footprint "eagle-import:_0402")
      (fields (field (name "PARTNO") "CRCW040210K0FKED"))
      (libsource (lib "eagle-import") (part "RESISTOR0402"))
    )
    (comp (ref "R3")
      (value "10k")
      (footprint "eagle-import:_0402")
      (fields (field (name "PARTNO") "CRCW040210K0FKED"))
      (libsource (lib "eagle-import") (part "RESISTOR0402"))
    )
    (comp (ref "R4")
      (value "10k")
      (footprint "eagle-import:_0402")
      (fields (field (name "PARTNO") "CRCW040210K0FKED"))
      (libsource (lib "eagle-import") (part "RESISTOR0402"))
    )
    (comp (ref "R5")
      (value "25")
      (footprint "eagle-import:_0402")
      (fields (field (name "PARTNO") "CRCW040224R9FKED"))
      (libsource (lib "eagle-import") (part "RESISTOR0402"))
    )
    (comp (ref "R6")
      (value "25")
      (footprint "eagle-import:_0402")
      (fields (field (name "PARTNO") "CRCW040224R9FKED"))
      (libsource (lib "eagle-import") (part "RESISTOR0402"))
    )
    (comp (ref "R7")
      (value "10k")
      (footprint "eagle-import:_0402")
      (fields (field (name "PARTNO") "CRCW040210K0FKED"))
      (libsource (lib "eagle-import") (part "RESISTOR0402"))
    )
    (comp (ref "R8")
      (value "10k")
      (footprint "eagle-import:_0402")
      (fields (field (name "PARTNO") "CRCW040210K0FKED"))
      (libsource (lib "eagle-import") (part "RESISTOR0402"))
    )
    (comp (ref "S1")
      (value "CUS-12TB")
      (footprint "eagle-import:SWITCH-SPST-SMD-A")
      (libsource (lib "eagle-import") (part "SWITCH-SPDT-SMD-A"))
    )
    (comp (ref "TP1")
      (value "TPPAD1-13")
      (footprint "eagle-import:P1-13")
      (fields (field (name "PARTNO") "TEST POINT"))
      (libsource (lib "eagle-import") (part "TPPAD1-13"))
    )
    (comp (ref "TP2")
      (value "TPPAD1-13")
      (footprint "eagle-import:P1-13")
      (fields (field (name "PARTNO") "TEST POINT"))
      (libsource (lib "eagle-import") (part "TPPAD1-13"))
    )
    (comp (ref "TP3")
      (value "TPPAD1-13")
      (footprint "eagle-import:P1-13")
      (fields (field (name "PARTNO") "TEST POINT"))
      (libsource (lib "eagle-import") (part "TPPAD1-13"))
    )
    (comp (ref "TP4")
      (value "TPPAD1-13")
      (footprint "eagle-import:P1-13")
      (fields (field (name "PARTNO") "TEST POINT"))
      (libsource (lib "eagle-import") (part "TPPAD1-13"))
    )
    (comp (ref "TP5")
      (value "TPPAD1-13")
      (footprint "eagle-import:P1-13")
      (fields (field (name "PARTNO") "TEST POINT"))
      (libsource (lib "eagle-import") (part "TPPAD1-13"))
    )
    (comp (ref "TP6")
      (value "TPPAD1-13")
      (footprint "eagle-import:P1-13")
      (fields (field (name "PARTNO") "TEST POINT"))
      (libsource (lib "eagle-import") (part "TPPAD1-13"))
    )
    (comp (ref "TP7")
      (value "TPPAD1-13")
      (footprint "eagle-import:P1-13")
      (fields (field (name "PARTNO") "TEST POINT"))
      (libsource (lib "eagle-import") (part "TPPAD1-13"))
    )
    (comp (ref "TP8")
      (value "TPPAD1-13")
      (footprint "eagle-import:P1-13")
      (fields (field (name "PARTNO") "TEST POINT"))
      (libsource (lib "eagle-import") (part "TPPAD1-13"))
    )
    (comp (ref "TP9")
      (value "TPPAD1-13")
      (footprint "eagle-import:P1-13")
      (fields (field (name "PARTNO") "TEST POINT"))
      (libsource (lib "eagle-import") (part "TPPAD1-13"))
    )
    (comp (ref "TP10")
      (value "TPPAD1-13")
      (footprint "eagle-import:P1-13")
      (fields (field (name "PARTNO") "TEST POINT"))
      (libsource (lib "eagle-import") (part "TPPAD1-13"))
    )
    (comp (ref "TP11")
      (value "TPPAD1-13")
      (footprint "eagle-import:P1-13")
      (fields (field (name "PARTNO") "TEST POINT"))
      (libsource (lib "eagle-import") (part "TPPAD1-13"))
    )
    (comp (ref "TP12")
      (value "TPPAD1-13")
      (footprint "eagle-import:P1-13")
      (fields (field (name "PARTNO") "TEST POINT"))
      (libsource (lib "eagle-import") (part "TPPAD1-13"))
    )
    (comp (ref "TP13")
      (value "TPPAD1-13")
      (footprint "eagle-import:P1-13")
      (fields (field (name "PARTNO") "TEST POINT"))
      (libsource (lib "eagle-import") (part "TPPAD1-13"))
    )
    (comp (ref "TP14")
      (value "TPPAD1-13")
      (footprint "eagle-import:P1-13")
      (fields (field (name "PARTNO") "TEST POINT"))
      (libsource (lib "eagle-import") (part "TPPAD1-13"))
    )
    (comp (ref "TP15")
      (value "TPPAD1-13")
      (footprint "eagle-import:P1-13")
      (fields (field (name "PARTNO") "TEST POINT"))
      (libsource (lib "eagle-import") (part "TPPAD1-13"))
    )
    (comp (ref "TP16")
      (value "TPPAD1-13")
      (footprint "eagle-import:P1-13")
      (fields (field (name "PARTNO") "TEST POINT"))
      (libsource (lib "eagle-import") (part "TPPAD1-13"))
    )
    (comp (ref "TP17")
      (value "TPPAD1-13")
      (footprint "eagle-import:P1-13")
      (fields (field (name "PARTNO") "TEST POINT"))
      (libsource (lib "eagle-import") (part "TPPAD1-13"))
    )
    (comp (ref "TP18")
      (value "TPPAD1-13")
      (footprint "eagle-import:P1-13")
      (fields (field (name "PARTNO") "TEST POINT"))
      (libsource (lib "eagle-import") (part "TPPAD1-13"))
    )
    (comp (ref "TP19")
      (value "TPPAD1-13")
      (footprint "eagle-import:P1-13")
      (fields (field (name "PARTNO") "TEST POINT"))
      (libsource (lib "eagle-import") (part "TPPAD1-13"))
    )
    (comp (ref "TP20")
      (value "TPPAD1-13")
      (footprint "eagle-import:P1-13")
      (fields (field (name "PARTNO") "TEST POINT"))
      (libsource (lib "eagle-import") (part "TPPAD1-13"))
    )
    (comp (ref "TP21")
      (value "TPPAD1-13")
      (footprint "eagle-import:P1-13")
      (fields (field (name "PARTNO") "TEST POINT"))
      (libsource (lib "eagle-import") (part "TPPAD1-13"))
    )
    (comp (ref "TP22")
      (value "TPPAD1-13")
      (footprint "eagle-import:P1-13")
      (fields (field (name "PARTNO") "TEST POINT"))
      (libsource (lib "eagle-import") (part "TPPAD1-13"))
    )
    (comp (ref "TP23")
      (value "TPPAD1-13")
      (footprint "eagle-import:P1-13")
      (fields (field (name "PARTNO") "TEST POINT"))
      (libsource (lib "eagle-import") (part "TPPAD1-13"))
    )
    (comp (ref "TP24")
      (value "TPPAD1-13")
      (footprint "eagle-import:P1-13")
      (fields (field (name "PARTNO") "TEST POINT"))
      (libsource (lib "eagle-import") (part "TPPAD1-13"))
    )
    (comp (ref "TP25")
      (value "TPPAD1-13")
      (footprint "eagle-import:P1-13")
      (fields (field (name "PARTNO") "TEST POINT"))
      (libsource (lib "eagle-import") (part "TPPAD1-13"))
    )
    (comp (ref "TP26")
      (value "TPPAD1-13")
      (footprint "eagle-import:P1-13")
      (fields (field (name "PARTNO") "TEST POINT"))
      (libsource (lib "eagle-import") (part "TPPAD1-13"))
    )
    (comp (ref "TP27")
      (value "TPPAD1-13")
      (footprint "eagle-import:P1-13")
      (fields (field (name "PARTNO") "TEST POINT"))
      (libsource (lib "eagle-import") (part "TPPAD1-13"))
    )
    (comp (ref "TP28")
      (value "TPPAD1-13")
      (footprint "eagle-import:P1-13")
      (fields (field (name "PARTNO") "TEST POINT"))
      (libsource (lib "eagle-import") (part "TPPAD1-13"))
    )
    (comp (ref "TP29")
      (value "TPPAD1-13")
      (footprint "eagle-import:P1-13")
      (fields (field (name "PARTNO") "TEST POINT"))
      (libsource (lib "eagle-import") (part "TPPAD1-13"))
    )
    (comp (ref "TP30")
      (value "TPPAD1-13")
      (footprint "eagle-import:P1-13")
      (fields (field (name "PARTNO") "TEST POINT"))
      (libsource (lib "eagle-import") (part "TPPAD1-13"))
    )
    (comp (ref "TP31")
      (value "TPPAD1-13")
      (footprint "eagle-import:P1-13")
      (fields (field (name "PARTNO") "TEST POINT"))
      (libsource (lib "eagle-import") (part "TPPAD1-13"))
    )
    (comp (ref "TP32")
      (value "TPPAD1-13")
      (footprint "eagle-import:P1-13")
      (fields (field (name "PARTNO") "TEST POINT"))
      (libsource (lib "eagle-import") (part "TPPAD1-13"))
    )
    (comp (ref "TP33")
      (value "TPPAD1-13")
      (footprint "eagle-import:P1-13")
      (fields (field (name "PARTNO") "TEST POINT"))
      (libsource (lib "eagle-import") (part "TPPAD1-13"))
    )
    (comp (ref "TP34")
      (value "TPPAD1-13")
      (footprint "eagle-import:P1-13")
      (fields (field (name "PARTNO") "TEST POINT"))
      (libsource (lib "eagle-import") (part "TPPAD1-13"))
    )
    (comp (ref "TP35")
      (value "TPPAD1-13")
      (footprint "eagle-import:P1-13")
      (fields (field (name "PARTNO") "TEST POINT"))
      (libsource (lib "eagle-import") (part "TPPAD1-13"))
    )
    (comp (ref "TP36")
      (value "TPPAD1-13")
      (footprint "eagle-import:P1-13")
      (fields (field (name "PARTNO") "TEST POINT"))
      (libsource (lib "eagle-import") (part "TPPAD1-13"))
    )
    (comp (ref "TP37")
      (value "TPTP08R")
      (footprint "eagle-import:TP08R")
      (fields (field (name "PARTNO") "TEST POINT"))
      (libsource (lib "eagle-import") (part "TPTP08R"))
    )
    (comp (ref "TP38")
      (value "TPTP08R")
      (footprint "eagle-import:TP08R")
      (fields (field (name "PARTNO") "TEST POINT"))
      (libsource (lib "eagle-import") (part "TPTP08R"))
    )
    (comp (ref "U1")
      (value "MK20DX256VLH7")
      (footprint "eagle-import:MK20DX256VLH7")
      (fields (field (name "MF") "Freescale"))
      (libsource (lib "eagle-import") (part "MK20DX256VLH7"))
    )
    (comp (ref "Y1")
      (value "8MHz")
      (footprint "eagle-import:ASCO")
      (fields (field (name "PARTNO") "ASCO-8.000MHZ-EK-T3"))
      (libsource (lib "eagle-import") (part "ASCO.063X.047"))
    )
    (comp (ref "Y2")
      (value "34.728kHz")
      (footprint "eagle-import:ABS06")
      (fields (field (name "PARTNO") "ABS06-32.768KHZ-T"))
      (libsource (lib "eagle-import") (part "ABS06ABS06_.079X.047"))
    )
  )
  (nets
    (net (code "1") (name "3.3V") (class "Default")
      (node (ref "C1") (pin "1") (pinfunction "1_1") (pintype "passive"))
      (node (ref "C11") (pin "1") (pinfunction "1_1") (pintype "passive"))
      (node (ref "C12") (pin "1") (pinfunction "1_1") (pintype "passive"))
      (node (ref "C13") (pin "1") (pinfunction "1_1") (pintype "passive"))
      (node (ref "C14") (pin "1") (pinfunction "1_1") (pintype "passive"))
      (node (ref "C16") (pin "2") (pinfunction "2_2") (pintype "passive"))
      (node (ref "C17") (pin "1") (pinfunction "1_1") (pintype "passive"))
      (node (ref "C19") (pin "1") (pinfunction "1_1") (pintype "passive"))
      (node (ref "C2") (pin "1") (pinfunction "1_1") (pintype "passive"))
      (node (ref "C20") (pin "2") (pinfunction "2_2") (pintype "passive"))
      (node (ref "C21") (pin "1") (pinfunction "1_1") (pintype "passive"))
      (node (ref "C22") (pin "1") (pinfunction "1_1") (pintype "passive"))
      (node (ref "C25") (pin "1") (pinfunction "1_1") (pintype "passive"))
      (node (ref "C26") (pin "1") (pinfunction "1_1") (pintype "passive"))
      (node (ref "C27") (pin "1") (pinfunction "1_1") (pintype "passive"))
      (node (ref "C3") (pin "1") (pinfunction "1_1") (pintype "passive"))
      (node (ref "C4") (pin "1") (pinfunction "1_1") (pintype "passive"))
      (node (ref "C5") (pin "1") (pinfunction "1_1") (pintype "passive"))
      (node (ref "DS10") (pin "4") (pinfunction "V_4") (pintype "bidirectional"))
      (node (ref "DS11") (pin "4") (pinfunction "V_4") (pintype "bidirectional"))
      (node (ref "DS12") (pin "4") (pinfunction "V_4") (pintype "bidirectional"))
      (node (ref "DS13") (pin "4") (pinfunction "V_4") (pintype "bidirectional"))
      (node (ref "DS14") (pin "4") (pinfunction "V_4") (pintype "bidirectional"))
      (node (ref "DS15") (pin "4") (pinfunction "V_4") (pintype "bidirectional"))
      (node (ref "DS4") (pin "4") (pinfunction "V_4") (pintype "bidirectional"))
      (node (ref "DS5") (pin "4") (pinfunction "V_4") (pintype "bidirectional"))
      (node (ref "DS6") (pin "4") (pinfunction "V_4") (pintype "bidirectional"))
      (node (ref "DS7") (pin "4") (pinfunction "V_4") (pintype "bidirectional"))
      (node (ref "DS8") (pin "4") (pinfunction "V_4") (pintype "bidirectional"))
      (node (ref "DS9") (pin "4") (pinfunction "V_4") (pintype "bidirectional"))
      (node (ref "J1") (pin "1") (pinfunction "VCC_1") (pintype "bidirectional"))
      (node (ref "L1") (pin "2") (pinfunction "2_2") (pintype "passive"))
      (node (ref "R1") (pin "1") (pinfunction "1_1") (pintype "passive"))
      (node (ref "R11") (pin "2") (pinfunction "2_2") (pintype "passive"))
      (node (ref "R13") (pin "1") (pinfunction "1_1") (pintype "passive"))
      (node (ref "R3") (pin "1") (pinfunction "1_1") (pintype "passive"))
      (node (ref "R4") (pin "1") (pinfunction "1_1") (pintype "passive"))
      (node (ref "R46") (pin "2") (pinfunction "2_2") (pintype "passive"))
      (node (ref "R5") (pin "1") (pinfunction "1_1") (pintype "passive"))
      (node (ref "R6") (pin "1") (pinfunction "1_1") (pintype "passive"))
      (node (ref "R7") (pin "1") (pinfunction "1_1") (pintype "passive"))
      (node (ref "R8") (pin "1") (pinfunction "1_1") (pintype "passive"))
      (node (ref "TP1") (pin "TP") (pinfunction "TP_TP") (pintype "input"))
      (node (ref "TP16") (pin "TP") (pinfunction "TP_TP") (pintype "input"))
      (node (ref "TP17") (pin "TP") (pinfunction "TP_TP") (pintype "input"))
      (node (ref "TP18") (pin "TP") (pinfunction "TP_TP") (pintype "input"))
      (node (ref "TP2") (pin "TP") (pinfunction "TP_TP") (pintype "input"))
      (node (ref "TP3") (pin "TP") (pinfunction "TP_TP") (pintype "input"))
      (node (ref "TP31") (pin "TP") (pinfunction "TP_TP") (pintype "input"))
      (node (ref "TP32") (pin "TP") (pinfunction "TP_TP") (pintype "input"))
      (node (ref "TP33") (pin "TP") (pinfunction "TP_TP") (pintype "input"))
      (node (ref "TP34") (pin "TP") (pinfunction "TP_TP") (pintype "input"))
      (node (ref "TP35") (pin "TP") (pinfunction "TP_TP") (pintype "input"))
      (node (ref "TP36") (pin "TP") (pinfunction "TP_TP") (pintype "input"))
      (node (ref "U1") (pin "21") (pinfunction "VBAT_21") (pintype "bidirectional"))
      (node (ref "U1") (pin "3") (pinfunction "VDD_3") (pintype "bidirectional"))
      (node (ref "U1") (pin "30") (pinfunction "VDD_30") (pintype "bidirectional"))
      (node (ref "U1") (pin "48") (pinfunction "VDD_48") (pintype "bidirectional"))
      (node (ref "U1") (pin "7") (pinfunction "VOUT33_7") (pintype "bidirectional"))
      (node (ref "U1") (pin "8") (pinfunction "VREGIN_8") (pintype "bidirectional"))
      (node (ref "U2") (pin "2") (pinfunction "VOUT_2") (pintype "passive"))
      (node (ref "U3") (pin "21") (pinfunction "VDD_21") (pintype "bidirectional"))
      (node (ref "U4") (pin "21") (pinfunction "VDD_21") (pintype "bidirectional"))
      (node (ref "U4") (pin "22") (pinfunction "A0_22") (pintype "bidirectional"))
      (node (ref "U5") (pin "1") (pinfunction "VDDIO_1") (pintype "bidirectional"))
      (node (ref "U5") (pin "13") (pinfunction "VDD_13") (pintype "bidirectional"))
      (node (ref "U5") (pin "8") (pinfunction "VDDIO_8") (pintype "bidirectional"))
      (node (ref "U6") (pin "1") (pinfunction "VDDA/1_1") (pintype "bidirectional"))
      (node (ref "U6") (pin "11") (pinfunction "VDDPST/11_11") (pintype "bidirectional"))
      (node (ref "U6") (pin "17") (pinfunction "VDDPST/17_17") (pintype "bidirectional"))
      (node (ref "U6") (pin "29") (pinfunction "VDDD/29_29") (pintype "bidirectional"))
      (node (ref "U6") (pin "3") (pinfunction "VDD3P3/3_3") (pintype "bidirectional"))
      (node (ref "U6") (pin "30") (pinfunction "VDDA/30_30") (pintype "bidirectional"))
      (node (ref "U6") (pin "4") (pinfunction "VDD3P3/4_4") (pintype "bidirectional"))
      (node (ref "U7") (pin "8") (pinfunction "VCC_8") (pintype "bidirectional"))
      (node (ref "U8") (pin "15") (pinfunction "VDD/15_15") (pintype "bidirectional"))
      (node (ref "U8") (pin "18") (pinfunction "VDD/18_18") (pintype "bidirectional"))
      (node (ref "U8") (pin "7") (pinfunction "VDD/7_7") (pintype "bidirectional"))
      (node (ref "Y1") (pin "VCC") (pinfunction "VCC_VCC") (pintype "bidirectional"))
    )
    (net (code "2") (name "CE") (class "Default")
      (node (ref "TP56") (pin "TP") (pinfunction "TP_TP") (pintype "input"))
      (node (ref "U1") (pin "64") (pinfunction "PTD7/UART0_TX_64") (pintype "bidirectional"))
      (node (ref "U8") (pin "1") (pinfunction "CE/1_1") (pintype "bidirectional"))
    )
    (net (code "3") (name "CHIP_EN") (class "Default")
      (node (ref "TP46") (pin "TP") (pinfunction "TP_TP") (pintype "input"))
      (node (ref "U1") (pin "44") (pinfunction "PTC1/ADC0_SE15_44") (pintype "bidirectional"))
      (node (ref "U6") (pin "7") (pinfunction "CHIP_EN/7_7") (pintype "bidirectional"))
    )
    (net (code "4") (name "CLK") (class "Default")
      (node (ref "R50") (pin "1") (pinfunction "1_1") (pintype "passive"))
      (node (ref "U7") (pin "6") (pinfunction "CLK_6") (pintype "bidirectional"))
    )
    (net (code "5") (name "CS") (class "Default")
      (node (ref "U6") (pin "20") (pinfunction "SD_CMD/20_20") (pintype "bidirectional"))
      (node (ref "U7") (pin "1") (pinfunction "CS#_1") (pintype "bidirectional"))
    )
    (net (code "6") (name "CSN") (class "Default")
      (node (ref "TP55") (pin "TP") (pinfunction "TP_TP") (pintype "input"))
      (node (ref "U1") (pin "63") (pinfunction "PTD6/UART0_RX_63") (pintype "bidirectional"))
      (node (ref "U8") (pin "2") (pinfunction "CSN/2_2") (pintype "bidirectional"))
    )
    (net (code "7") (name "DIO") (class "Default")
      (node (ref "U6") (pin "23") (pinfunction "SD_DATA_1/23_23") (pintype "bidirectional"))
      (node (ref "U7") (pin "5") (pinfunction "DIO_5") (pintype "bidirectional"))
    )
    (net (code "8") (name "DO") (class "Default")
      (node (ref "U6") (pin "22") (pinfunction "SD_DATA_0/22_22") (pintype "bidirectional"))
      (node (ref "U7") (pin "2") (pinfunction "DO_2") (pintype "bidirectional"))
    )
    (net (code "9") (name "FSYNC") (class "Default")
      (node (ref "TP41") (pin "TP") (pinfunction "TP_TP") (pintype "input"))
      (node (ref "U1") (pin "55") (pinfunction "PTC10/ADC1_SE6B_55") (pintype "bidirectional"))
      (node (ref "U5") (pin "11") (pinfunction "FSYNC_11") (pintype "bidirectional"))
    )
    (net (code "10") (name "GND") (class "Default")
      (node (ref "C1") (pin "2") (pinfunction "2_2") (pintype "passive"))
      (node (ref "C10") (pin "2") (pinfunction "2_2") (pintype "passive"))
      (node (ref "C11") (pin "2") (pinfunction "2_2") (pintype "passive"))
      (node (ref "C12") (pin "2") (pinfunction "2_2") (pintype "passive"))
      (node (ref "C13") (pin "2") (pinfunction "2_2") (pintype "passive"))
      (node (ref "C14") (pin "2") (pinfunction "2_2") (pintype "passive"))
      (node (ref "C15") (pin "1") (pinfunction "1_1") (pintype "passive"))
      (node (ref "C16") (pin "1") (pinfunction "1_1") (pintype "passive"))
      (node (ref "C17") (pin "2") (pinfunction "2_2") (pintype "passive"))
      (node (ref "C19") (pin "2") (pinfunction "2_2") (pintype "passive"))
      (node (ref "C2") (pin "2") (pinfunction "2_2") (pintype "passive"))
      (node (ref "C20") (pin "1") (pinfunction "1_1") (pintype "passive"))
      (node (ref "C21") (pin "2") (pinfunction "2_2") (pintype "passive"))
      (node (ref "C22") (pin "2") (pinfunction "2_2") (pintype "passive"))
      (node (ref "C23") (pin "2") (pinfunction "2_2") (pintype "passive"))
      (node (ref "C24") (pin "2") (pinfunction "2_2") (pintype "passive"))
      (node (ref "C25") (pin "2") (pinfunction "2_2") (pintype "passive"))
      (node (ref "C26") (pin "2") (pinfunction "2_2") (pintype "passive"))
      (node (ref "C27") (pin "2") (pinfunction "2_2") (pintype "passive"))
      (node (ref "C28") (pin "1") (pinfunction "1_1") (pintype "passive"))
      (node (ref "C29") (pin "2") (pinfunction "2_2") (pintype "passive"))
      (node (ref "C3") (pin "2") (pinfunction "2_2") (pintype "passive"))
      (node (ref "C30") (pin "2") (pinfunction "2_2") (pintype "passive"))
      (node (ref "C31") (pin "2") (pinfunction "2_2") (pintype "passive"))
      (node (ref "C32") (pin "2") (pinfunction "2_2") (pintype "passive"))
      (node (ref "C34") (pin "2") (pinfunction "2_2") (pintype "passive"))
      (node (ref "C4") (pin "2") (pinfunction "2_2") (pintype "passive"))
      (node (ref "C5") (pin "2") (pinfunction "2_2") (pintype "passive"))
      (node (ref "C6") (pin "2") (pinfunction "2_2") (pintype "passive"))
      (node (ref "C7") (pin "2") (pinfunction "2_2") (pintype "passive"))
      (node (ref "C8") (pin "2") (pinfunction "2_2") (pintype "passive"))
      (node (ref "C9") (pin "2") (pinfunction "2_2") (pintype "passive"))
      (node (ref "DS3") (pin "C") (pinfunction "C_C") (pintype "passive"))
      (node (ref "J1") (pin "3") (pinfunction "GND_3") (pintype "bidirectional"))
      (node (ref "J1") (pin "5") (pinfunction "GND_5") (pintype "bidirectional"))
      (node (ref "J1") (pin "9") (pinfunction "GND-DETECT_9") (pintype "bidirectional"))
      (node (ref "JP1") (pin "2") (pinfunction "2_2") (pintype "passive"))
      (node (ref "L3") (pin "2") (pinfunction "2_2") (pintype "passive"))
      (node (ref "L4") (pin "2") (pinfunction "2_2") (pintype "passive"))
      (node (ref "R10") (pin "1") (pinfunction "1_1") (pintype "passive"))
      (node (ref "R12") (pin "1") (pinfunction "1_1") (pintype "passive"))
      (node (ref "R2") (pin "1") (pinfunction "1_1") (pintype "passive"))
      (node (ref "R47") (pin "2") (pinfunction "2_2") (pintype "passive"))
      (node (ref "R48") (pin "1") (pinfunction "1_1") (pintype "passive"))
      (node (ref "R49") (pin "1") (pinfunction "1_1") (pintype "passive"))
      (node (ref "R52") (pin "2") (pinfunction "2_2") (pintype "passive"))
      (node (ref "TP13") (pin "TP") (pinfunction "TP_TP") (pintype "input"))
      (node (ref "TP14") (pin "TP") (pinfunction "TP_TP") (pintype "input"))
      (node (ref "TP15") (pin "TP") (pinfunction "TP_TP") (pintype "input"))
      (node (ref "TP25") (pin "TP") (pinfunction "TP_TP") (pintype "input"))
      (node (ref "TP26") (pin "TP") (pinfunction "TP_TP") (pintype "input"))
      (node (ref "TP27") (pin "TP") (pinfunction "TP_TP") (pintype "input"))
      (node (ref "TP28") (pin "TP") (pinfunction "TP_TP") (pintype "input"))
      (node (ref "TP29") (pin "TP") (pinfunction "TP_TP") (pintype "input"))
      (node (ref "TP30") (pin "TP") (pinfunction "TP_TP") (pintype "input"))
      (node (ref "TP4") (pin "TP") (pinfunction "TP_TP") (pintype "input"))
      (node (ref "TP5") (pin "TP") (pinfunction "TP_TP") (pintype "input"))
      (node (ref "TP6") (pin "TP") (pinfunction "TP_TP") (pintype "input"))
      (node (ref "U1") (pin "15") (pinfunction "VREFL_15") (pintype "bidirectional"))
      (node (ref "U1") (pin "16") (pinfunction "VSSA_16") (pintype "bidirectional"))
      (node (ref "U1") (pin "31") (pinfunction "VSS_31") (pintype "bidirectional"))
      (node (ref "U1") (pin "4") (pinfunction "VSS_4") (pintype "bidirectional"))
      (node (ref "U1") (pin "47") (pinfunction "VSS_47") (pintype "bidirectional"))
      (node (ref "U2") (pin "11") (pinfunction "PAD_11") (pintype "power_in"))
      (node (ref "U2") (pin "12") (pinfunction "PAD_12") (pintype "power_in"))
      (node (ref "U2") (pin "13") (pinfunction "PAD_13") (pintype "power_in"))
      (node (ref "U2") (pin "14") (pinfunction "PAD_14") (pintype "power_in"))
      (node (ref "U2") (pin "15") (pinfunction "PAD_15") (pintype "power_in"))
      (node (ref "U2") (pin "4") (pinfunction "PGND_4") (pintype "power_in"))
      (node (ref "U2") (pin "9") (pinfunction "GND_9") (pintype "power_in"))
      (node (ref "U3") (pin "22") (pinfunction "A0_22") (pintype "bidirectional"))
      (node (ref "U3") (pin "23") (pinfunction "A1_23") (pintype "bidirectional"))
      (node (ref "U3") (pin "24") (pinfunction "A2_24") (pintype "bidirectional"))
      (node (ref "U3") (pin "9") (pinfunction "VSS_9") (pintype "bidirectional"))
      (node (ref "U4") (pin "23") (pinfunction "A1_23") (pintype "bidirectional"))
      (node (ref "U4") (pin "24") (pinfunction "A2_24") (pintype "bidirectional"))
      (node (ref "U4") (pin "9") (pinfunction "VSS_9") (pintype "bidirectional"))
      (node (ref "U5") (pin "14") (pinfunction "NC_PINS_2-6_14-17_14") (pintype "bidirectional"))
      (node (ref "U5") (pin "15") (pinfunction "NC_PINS_2-6_14-17_15") (pintype "bidirectional"))
      (node (ref "U5") (pin "16") (pinfunction "NC_PINS_2-6_14-17_16") (pintype "bidirectional"))
      (node (ref "U5") (pin "17") (pinfunction "NC_PINS_2-6_14-17_17") (pintype "bidirectional"))
      (node (ref "U5") (pin "18") (pinfunction "GND_18") (pintype "bidirectional"))
      (node (ref "U5") (pin "2") (pinfunction "NC_PINS_2-6_14-17_2") (pintype "bidirectional"))
      (node (ref "U5") (pin "20") (pinfunction "GND_20") (pintype "bidirectional"))
      (node (ref "U5") (pin "3") (pinfunction "NC_PINS_2-6_14-17_3") (pintype "bidirectional"))
      (node (ref "U5") (pin "4") (pinfunction "NC_PINS_2-6_14-17_4") (pintype "bidirectional"))
      (node (ref "U5") (pin "5") (pinfunction "NC_PINS_2-6_14-17_5") (pintype "bidirectional"))
      (node (ref "U5") (pin "6") (pinfunction "NC_PINS_2-6_14-17_6") (pintype "bidirectional"))
      (node (ref "U5") (pin "9") (pinfunction "AD0/MISO_9") (pintype "bidirectional"))
      (node (ref "U6") (pin "PAD") (pinfunction "PGND_PAD") (pintype "bidirectional"))
      (node (ref "U7") (pin "4") (pinfunction "GND_4") (pintype "bidirectional"))
      (node (ref "U8") (pin "14") (pinfunction "VSS/14_14") (pintype "bidirectional"))
      (node (ref "U8") (pin "17") (pinfunction "VSS/17_17") (pintype "bidirectional"))
      (node (ref "U8") (pin "20") (pinfunction "VSS/20_20") (pintype "bidirectional"))
      (node (ref "U8") (pin "8") (pinfunction "VSS/8_8") (pintype "bidirectional"))
      (node (ref "Y1") (pin "GND") (pinfunction "GND_GND") (pintype "bidirectional"))
    )
    (net (code "11") (name "GPIO0") (class "Default")
      (node (ref "TP49") (pin "TP") (pinfunction "TP_TP") (pintype "input"))
      (node (ref "U1") (pin "41") (pinfunction "PTB18/CAN0_RX_41") (pintype "bidirectional"))
      (node (ref "U6") (pin "15") (pinfunction "GPIO0/15_15") (pintype "bidirectional"))
    )
    (net (code "12") (name "GPIO2") (class "Default")
      (node (ref "TP47") (pin "TP") (pinfunction "TP_TP") (pintype "input"))
      (node (ref "U1") (pin "42") (pinfunction "PTB19/CAN0_TX_42") (pintype "bidirectional"))
      (node (ref "U6") (pin "14") (pinfunction "GPIO2/14_14") (pintype "bidirectional"))
    )
    (net (code "13") (name "HOLD#") (class "Default")
      (node (ref "U6") (pin "18") (pinfunction "SD_DATA_2/18_18") (pintype "bidirectional"))
      (node (ref "U7") (pin "7") (pinfunction "HOLD#_7") (pintype "bidirectional"))
    )
    (net (code "14") (name "INT") (class "Default")
      (node (ref "TP43") (pin "TP") (pinfunction "TP_TP") (pintype "input"))
      (node (ref "U1") (pin "54") (pinfunction "PTC9/ADC1_SE5B_54") (pintype "bidirectional"))
      (node (ref "U5") (pin "12") (pinfunction "INT_12") (pintype "bidirectional"))
    )
    (net (code "15") (name "IRQ") (class "Default")
      (node (ref "TP51") (pin "TP") (pinfunction "TP_TP") (pintype "input"))
      (node (ref "U1") (pin "53") (pinfunction "PTC8/ADC1_SE4B_53") (pintype "bidirectional"))
      (node (ref "U8") (pin "6") (pinfunction "IRQ/6_6") (pintype "bidirectional"))
    )
    (net (code "16") (name "MISO") (class "Default")
      (node (ref "TP52") (pin "TP") (pinfunction "TP_TP") (pintype "input"))
      (node (ref "U1") (pin "60") (pinfunction "PTD3/SPI0_SIN_60") (pintype "bidirectional"))
      (node (ref "U8") (pin "5") (pinfunction "MISO/5_5") (pintype "bidirectional"))
    )
    (net (code "17") (name "MOSI") (class "Default")
      (node (ref "TP53") (pin "TP") (pinfunction "TP_TP") (pintype "input"))
      (node (ref "U1") (pin "59") (pinfunction "PTD2/SPI0_SOUT_59") (pintype "bidirectional"))
      (node (ref "U8") (pin "4") (pinfunction "MOSI/4_4") (pintype "bidirectional"))
    )
    (net (code "18") (name "Net-(AE1-SIGNAL)") (class "Default")
      (node (ref "AE1") (pin "FEED") (pinfunction "SIGNAL_FEED") (pintype "bidirectional"))
      (node (ref "C18") (pin "1") (pinfunction "1_1") (pintype "passive"))
      (node (ref "L3") (pin "1") (pinfunction "1_1") (pintype "passive"))
    )
    (net (code "19") (name "Net-(AE2-SIGNAL)") (class "Default")
      (node (ref "AE2") (pin "FEED") (pinfunction "SIGNAL_FEED") (pintype "bidirectional"))
      (node (ref "C33") (pin "2") (pinfunction "2_2") (pintype "passive"))
      (node (ref "C34") (pin "1") (pinfunction "1_1") (pintype "passive"))
    )
    (net (code "20") (name "Net-(C33-Pad1)") (class "Default")
      (node (ref "C33") (pin "1") (pinfunction "1_1") (pintype "passive"))
      (node (ref "L7") (pin "2") (pinfunction "2_2") (pintype "passive"))
    )
    (net (code "21") (name "Net-(DS1-PadA)") (class "Default")
      (node (ref "DS1") (pin "A") (pinfunction "A_A") (pintype "passive"))
      (node (ref "R5") (pin "2") (pinfunction "2_2") (pintype "passive"))
    )
    (net (code "22") (name "Net-(DS2-PadA)") (class "Default")
      (node (ref "DS2") (pin "A") (pinfunction "A_A") (pintype "passive"))
      (node (ref "R6") (pin "2") (pinfunction "2_2") (pintype "passive"))
    )
    (net (code "23") (name "Net-(DS3-PadA)") (class "Default")
      (node (ref "DS3") (pin "A") (pinfunction "A_A") (pintype "passive"))
      (node (ref "R13") (pin "2") (pinfunction "2_2") (pintype "passive"))
    )
    (net (code "24") (name "Net-(DS4-B)") (class "Default")
      (node (ref "DS4") (pin "1") (pinfunction "B_1") (pintype "bidirectional"))
      (node (ref "R16") (pin "2") (pinfunction "2_2") (pintype "passive"))
    )
    (net (code "25") (name "Net-(DS4-G)") (class "Default")
      (node (ref "DS4") (pin "3") (pinfunction "G_3") (pintype "bidirectional"))
      (node (ref "R14") (pin "2") (pinfunction "2_2") (pintype "passive"))
    )
    (net (code "26") (name "Net-(DS4-R)") (class "Default")
      (node (ref "DS4") (pin "2") (pinfunction "R_2") (pintype "bidirectional"))
      (node (ref "R15") (pin "2") (pinfunction "2_2") (pintype "passive"))
    )
    (net (code "27") (name "Net-(DS5-B)") (class "Default")
      (node (ref "DS5") (pin "1") (pinfunction "B_1") (pintype "bidirectional"))
      (node (ref "R19") (pin "2") (pinfunction "2_2") (pintype "passive"))
    )
    (net (code "28") (name "Net-(DS5-G)") (class "Default")
      (node (ref "DS5") (pin "3") (pinfunction "G_3") (pintype "bidirectional"))
      (node (ref "R17") (pin "2") (pinfunction "2_2") (pintype "passive"))
    )
    (net (code "29") (name "Net-(DS5-R)") (class "Default")
      (node (ref "DS5") (pin "2") (pinfunction "R_2") (pintype "bidirectional"))
      (node (ref "R18") (pin "2") (pinfunction "2_2") (pintype "passive"))
    )
    (net (code "30") (name "Net-(DS6-B)") (class "Default")
      (node (ref "DS6") (pin "1") (pinfunction "B_1") (pintype "bidirectional"))
      (node (ref "R21") (pin "2") (pinfunction "2_2") (pintype "passive"))
    )
    (net (code "31") (name "Net-(DS6-G)") (class "Default")
      (node (ref "DS6") (pin "3") (pinfunction "G_3") (pintype "bidirectional"))
      (node (ref "R20") (pin "2") (pinfunction "2_2") (pintype "passive"))
    )
    (net (code "32") (name "Net-(DS7-B)") (class "Default")
      (node (ref "DS7") (pin "1") (pinfunction "B_1") (pintype "bidirectional"))
      (node (ref "R24") (pin "2") (pinfunction "2_2") (pintype "passive"))
    )
    (net (code "33") (name "Net-(DS7-G)") (class "Default")
      (node (ref "DS7") (pin "3") (pinfunction "G_3") (pintype "bidirectional"))
      (node (ref "R22") (pin "2") (pinfunction "2_2") (pintype "passive"))
    )
    (net (code "34") (name "Net-(DS7-R)") (class "Default")
      (node (ref "DS7") (pin "2") (pinfunction "R_2") (pintype "bidirectional"))
      (node (ref "R23") (pin "2") (pinfunction "2_2") (pintype "passive"))
    )
    (net (code "35") (name "Net-(DS8-B)") (class "Default")
      (node (ref "DS8") (pin "1") (pinfunction "B_1") (pintype "bidirectional"))
      (node (ref "R27") (pin "2") (pinfunction "2_2") (pintype "passive"))
    )
    (net (code "36") (name "Net-(DS8-G)") (class "Default")
      (node (ref "DS8") (pin "3") (pinfunction "G_3") (pintype "bidirectional"))
      (node (ref "R25") (pin "2") (pinfunction "2_2") (pintype "passive"))
    )
    (net (code "37") (name "Net-(DS8-R)") (class "Default")
      (node (ref "DS8") (pin "2") (pinfunction "R_2") (pintype "bidirectional"))
      (node (ref "R26") (pin "2") (pinfunction "2_2") (pintype "passive"))
    )
    (net (code "38") (name "Net-(DS9-B)") (class "Default")
      (node (ref "DS9") (pin "1") (pinfunction "B_1") (pintype "bidirectional"))
      (node (ref "R29") (pin "2") (pinfunction "2_2") (pintype "passive"))
    )
    (net (code "39") (name "Net-(DS9-G)") (class "Default")
      (node (ref "DS9") (pin "3") (pinfunction "G_3") (pintype "bidirectional"))
      (node (ref "R28") (pin "2") (pinfunction "2_2") (pintype "passive"))
    )
    (net (code "40") (name "Net-(DS10-B)") (class "Default")
      (node (ref "DS10") (pin "1") (pinfunction "B_1") (pintype "bidirectional"))
      (node (ref "R30") (pin "2") (pinfunction "2_2") (pintype "passive"))
    )
    (net (code "41") (name "Net-(DS10-G)") (class "Default")
      (node (ref "DS10") (pin "3") (pinfunction "G_3") (pintype "bidirectional"))
      (node (ref "R31") (pin "2") (pinfunction "2_2") (pintype "passive"))
    )
    (net (code "42") (name "Net-(DS11-B)") (class "Default")
      (node (ref "DS11") (pin "1") (pinfunction "B_1") (pintype "bidirectional"))
      (node (ref "R32") (pin "2") (pinfunction "2_2") (pintype "passive"))
    )
    (net (code "43") (name "Net-(DS11-G)") (class "Default")
      (node (ref "DS11") (pin "3") (pinfunction "G_3") (pintype "bidirectional"))
      (node (ref "R34") (pin "2") (pinfunction "2_2") (pintype "passive"))
    )
    (net (code "44") (name "Net-(DS11-R)") (class "Default")
      (node (ref "DS11") (pin "2") (pinfunction "R_2") (pintype "bidirectional"))
      (node (ref "R33") (pin "2") (pinfunction "2_2") (pintype "passive"))
    )
    (net (code "45") (name "Net-(DS12-B)") (class "Default")
      (node (ref "DS12") (pin "1") (pinfunction "B_1") (pintype "bidirectional"))
      (node (ref "R35") (pin "2") (pinfunction "2_2") (pintype "passive"))
    )
    (net (code "46") (name "Net-(DS12-G)") (class "Default")
      (node (ref "DS12") (pin "3") (pinfunction "G_3") (pintype "bidirectional"))
      (node (ref "R37") (pin "2") (pinfunction "2_2") (pintype "passive"))
    )
    (net (code "47") (name "Net-(DS12-R)") (class "Default")
      (node (ref "DS12") (pin "2") (pinfunction "R_2") (pintype "bidirectional"))
      (node (ref "R36") (pin "2") (pinfunction "2_2") (pintype "passive"))
    )
    (net (code "48") (name "Net-(DS13-B)") (class "Default")
      (node (ref "DS13") (pin "1") (pinfunction "B_1") (pintype "bidirectional"))
      (node (ref "R38") (pin "2") (pinfunction "2_2") (pintype "passive"))
    )
    (net (code "49") (name "Net-(DS13-G)") (class "Default")
      (node (ref "DS13") (pin "3") (pinfunction "G_3") (pintype "bidirectional"))
      (node (ref "R39") (pin "2") (pinfunction "2_2") (pintype "passive"))
    )
    (net (code "50") (name "Net-(DS14-B)") (class "Default")
      (node (ref "DS14") (pin "1") (pinfunction "B_1") (pintype "bidirectional"))
      (node (ref "R40") (pin "2") (pinfunction "2_2") (pintype "passive"))
    )
    (net (code "51") (name "Net-(DS14-G)") (class "Default")
      (node (ref "DS14") (pin "3") (pinfunction "G_3") (pintype "bidirectional"))
      (node (ref "R42") (pin "2") (pinfunction "2_2") (pintype "passive"))
    )
    (net (code "52") (name "Net-(DS14-R)") (class "Default")
      (node (ref "DS14") (pin "2") (pinfunction "R_2") (pintype "bidirectional"))
      (node (ref "R41") (pin "2") (pinfunction "2_2") (pintype "passive"))
    )
    (net (code "53") (name "Net-(DS15-B)") (class "Default")
      (node (ref "DS15") (pin "1") (pinfunction "B_1") (pintype "bidirectional"))
      (node (ref "R43") (pin "2") (pinfunction "2_2") (pintype "passive"))
    )
    (net (code "54") (name "Net-(DS15-G)") (class "Default")
      (node (ref "DS15") (pin "3") (pinfunction "G_3") (pintype "bidirectional"))
      (node (ref "R45") (pin "2") (pinfunction "2_2") (pintype "passive"))
    )
    (net (code "55") (name "Net-(DS15-R)") (class "Default")
      (node (ref "DS15") (pin "2") (pinfunction "R_2") (pintype "bidirectional"))
      (node (ref "R44") (pin "2") (pinfunction "2_2") (pintype "passive"))
    )
    (net (code "56") (name "Net-(J1-NC{slash}TDI)") (class "Default")
      (node (ref "J1") (pin "8") (pinfunction "NC/TDI_8") (pintype "bidirectional"))
      (node (ref "R3") (pin "2") (pinfunction "2_2") (pintype "passive"))
      (node (ref "U1") (pin "23") (pinfunction "PTA1/TDI_23") (pintype "bidirectional"))
    )
    (net (code "57") (name "Net-(J1-SWDCLK{slash}TCK)") (class "Default")
      (node (ref "J1") (pin "4") (pinfunction "SWDCLK/TCK_4") (pintype "bidirectional"))
      (node (ref "R2") (pin "2") (pinfunction "2_2") (pintype "passive"))
      (node (ref "U1") (pin "22") (pinfunction "PTA0/TCLK_22") (pintype "bidirectional"))
    )
    (net (code "58") (name "Net-(J1-SWDIO{slash}TMS)") (class "Default")
      (node (ref "J1") (pin "2") (pinfunction "SWDIO/TMS_2") (pintype "bidirectional"))
      (node (ref "R1") (pin "2") (pinfunction "2_2") (pintype "passive"))
      (node (ref "U1") (pin "25") (pinfunction "PTA3/TMS_25") (pintype "bidirectional"))
    )
    (net (code "59") (name "Net-(J1-SWO{slash}TDO)") (class "Default")
      (node (ref "J1") (pin "6") (pinfunction "SWO/TDO_6") (pintype "bidirectional"))
      (node (ref "U1") (pin "24") (pinfunction "PTA2/TDO_24") (pintype "bidirectional"))
    )
    (net (code "60") (name "Net-(J1-~{RESET})") (class "Default")
      (node (ref "J1") (pin "10") (pinfunction "~{RESET}_10") (pintype "bidirectional"))
      (node (ref "R4") (pin "2") (pinfunction "2_2") (pintype "passive"))
      (node (ref "U1") (pin "34") (pinfunction "RESET_B_34") (pintype "bidirectional"))
    )
    (net (code "61") (name "Net-(S1-P)") (class "Default")
      (node (ref "JP1") (pin "1") (pinfunction "1_1") (pintype "passive"))
      (node (ref "S1") (pin "2") (pinfunction "P_2") (pintype "passive"))
    )
    (net (code "62") (name "Net-(U1-EXTAL32)") (class "Default")
      (node (ref "U1") (pin "20") (pinfunction "EXTAL32_20") (pintype "bidirectional"))
      (node (ref "Y2") (pin "P$1") (pinfunction "1_P$1") (pintype "bidirectional"))
    )
    (net (code "63") (name "Net-(U1-PTA4)") (class "Default")
      (node (ref "TP21") (pin "TP") (pinfunction "TP_TP") (pintype "input"))
      (node (ref "U1") (pin "26") (pinfunction "PTA4_26") (pintype "bidirectional"))
    )
    (net (code "64") (name "Net-(U1-PTA12{slash}CAN0_TX)") (class "Default")
      (node (ref "TP20") (pin "TP") (pinfunction "TP_TP") (pintype "input"))
      (node (ref "U1") (pin "28") (pinfunction "PTA12/CAN0_TX_28") (pintype "bidirectional"))
    )
    (net (code "65") (name "Net-(U1-PTA13{slash}CAN0_RX)") (class "Default")
      (node (ref "TP19") (pin "TP") (pinfunction "TP_TP") (pintype "input"))
      (node (ref "U1") (pin "29") (pinfunction "PTA13/CAN0_RX_29") (pintype "bidirectional"))
    )
    (net (code "66") (name "Net-(U1-PTA18{slash}EXTAL0)") (class "Default")
      (node (ref "U1") (pin "32") (pinfunction "PTA18/EXTAL0_32") (pintype "bidirectional"))
      (node (ref "Y1") (pin "OUT") (pinfunction "OUT_OUT") (pintype "bidirectional"))
    )
    (net (code "67") (name "Net-(U1-PTA19{slash}XTAL0)") (class "Default")
      (node (ref "U1") (pin "33") (pinfunction "PTA19/XTAL0_33") (pintype "bidirectional"))
      (node (ref "Y1") (pin "ENABLE") (pinfunction "ENABLE_ENABLE") (pintype "bidirectional"))
    )
    (net (code "68") (name "Net-(U1-PTB0{slash}ADC0_SE8)") (class "Default")
      (node (ref "TP12") (pin "TP") (pinfunction "TP_TP") (pintype "input"))
      (node (ref "U1") (pin "35") (pinfunction "PTB0/ADC0_SE8_35") (pintype "bidirectional"))
    )
    (net (code "69") (name "Net-(U1-PTB1{slash}ADC0_SE9)") (class "Default")
      (node (ref "TP11") (pin "TP") (pinfunction "TP_TP") (pintype "input"))
      (node (ref "U1") (pin "36") (pinfunction "PTB1/ADC0_SE9_36") (pintype "bidirectional"))
    )
    (net (code "70") (name "Net-(U1-PTC2{slash}SPI0_PCS2)") (class "Default")
      (node (ref "TP10") (pin "TP") (pinfunction "TP_TP") (pintype "input"))
      (node (ref "U1") (pin "45") (pinfunction "PTC2/SPI0_PCS2_45") (pintype "bidirectional"))
    )
    (net (code "71") (name "Net-(U1-PTC5{slash}SPI0_SCK)") (class "Default")
      (node (ref "TP9") (pin "TP") (pinfunction "TP_TP") (pintype "input"))
      (node (ref "U1") (pin "50") (pinfunction "PTC5/SPI0_SCK_50") (pintype "bidirectional"))
    )
    (net (code "72") (name "Net-(U1-PTC6{slash}SPI0_SOUT)") (class "Default")
      (node (ref "TP8") (pin "TP") (pinfunction "TP_TP") (pintype "input"))
      (node (ref "U1") (pin "51") (pinfunction "PTC6/SPI0_SOUT_51") (pintype "bidirectional"))
    )
    (net (code "73") (name "Net-(U1-PTC7{slash}SPI0_SIN)") (class "Default")
      (node (ref "TP7") (pin "TP") (pinfunction "TP_TP") (pintype "input"))
      (node (ref "U1") (pin "52") (pinfunction "PTC7/SPI0_SIN_52") (pintype "bidirectional"))
    )
    (net (code "74") (name "Net-(U1-PTD0{slash}SPI0_PCS0)") (class "Default")
      (node (ref "TP24") (pin "TP") (pinfunction "TP_TP") (pintype "input"))
      (node (ref "U1") (pin "57") (pinfunction "PTD0/SPI0_PCS0_57") (pintype "bidirectional"))
    )
    (net (code "75") (name "Net-(U1-PTD4{slash}SPI0_PCS1)") (class "Default")
      (node (ref "DS2") (pin "C") (pinfunction "C_C") (pintype "passive"))
      (node (ref "U1") (pin "61") (pinfunction "PTD4/SPI0_PCS1_61") (pintype "bidirectional"))
    )
    (net (code "76") (name "Net-(U1-PTD5{slash}SPI0_PCS2)") (class "Default")
      (node (ref "DS1") (pin "C") (pinfunction "C_C") (pintype "passive"))
      (node (ref "U1") (pin "62") (pinfunction "PTD5/SPI0_PCS2_62") (pintype "bidirectional"))
    )
    (net (code "77") (name "Net-(U1-PTE0{slash}I2C1_SDA{slash}UART1_TX)") (class "Default")
      (node (ref "TP23") (pin "TP") (pinfunction "TP_TP") (pintype "input"))
      (node (ref "U1") (pin "1") (pinfunction "PTE0/I2C1_SDA/UART1_TX_1") (pintype "bidirectional"))
    )
    (net (code "78") (name "Net-(U1-PTE1{slash}I2C1_SCL{slash}UART1_RX)") (class "Default")
      (node (ref "TP22") (pin "TP") (pinfunction "TP_TP") (pintype "input"))
      (node (ref "U1") (pin "2") (pinfunction "PTE1/I2C1_SCL/UART1_RX_2") (pintype "bidirectional"))
    )
    (net (code "79") (name "Net-(U1-VDDA)") (class "Default")
      (node (ref "C6") (pin "1") (pinfunction "1_1") (pintype "passive"))
      (node (ref "C7") (pin "1") (pinfunction "1_1") (pintype "passive"))
      (node (ref "L1") (pin "1") (pinfunction "1_1") (pintype "passive"))
      (node (ref "U1") (pin "13") (pinfunction "VDDA_13") (pintype "bidirectional"))
      (node (ref "U1") (pin "14") (pinfunction "VREFH_14") (pintype "bidirectional"))
    )
    (net (code "80") (name "Net-(U1-VREF_OUT)") (class "Default")
      (node (ref "C8") (pin "1") (pinfunction "1_1") (pintype "passive"))
      (node (ref "U1") (pin "17") (pinfunction "VREF_OUT_17") (pintype "bidirectional"))
    )
    (net (code "81") (name "Net-(U1-XTAL32)") (class "Default")
      (node (ref "U1") (pin "19") (pinfunction "XTAL32_19") (pintype "bidirectional"))
      (node (ref "Y2") (pin "P$2") (pinfunction "2_P$2") (pintype "bidirectional"))
    )
    (net (code "82") (name "Net-(U2-FB)") (class "Default")
      (node (ref "R11") (pin "1") (pinfunction "1_1") (pintype "passive"))
      (node (ref "R12") (pin "2") (pinfunction "2_2") (pintype "passive"))
      (node (ref "U2") (pin "10") (pinfunction "FB_10") (pintype "passive"))
    )
    (net (code "83") (name "Net-(U2-L)") (class "Default")
      (node (ref "L2") (pin "1") (pinfunction "1_1") (pintype "passive"))
      (node (ref "U2") (pin "3") (pinfunction "L_3") (pintype "passive"))
    )
    (net (code "84") (name "Net-(U2-UVLO)") (class "Default")
      (node (ref "R10") (pin "2") (pinfunction "2_2") (pintype "passive"))
      (node (ref "R9") (pin "1") (pinfunction "1_1") (pintype "passive"))
      (node (ref "U2") (pin "7") (pinfunction "UVLO_7") (pintype "passive"))
    )
    (net (code "85") (name "Net-(U2-VAUX)") (class "Default")
      (node (ref "C10") (pin "1") (pinfunction "1_1") (pintype "passive"))
      (node (ref "U2") (pin "1") (pinfunction "VAUX_1") (pintype "passive"))
    )
    (net (code "86") (name "Net-(U3-LED0)") (class "Default")
      (node (ref "R14") (pin "1") (pinfunction "1_1") (pintype "passive"))
      (node (ref "U3") (pin "1") (pinfunction "LED0_1") (pintype "bidirectional"))
    )
    (net (code "87") (name "Net-(U3-LED1)") (class "Default")
      (node (ref "R15") (pin "1") (pinfunction "1_1") (pintype "passive"))
      (node (ref "U3") (pin "2") (pinfunction "LED1_2") (pintype "bidirectional"))
    )
    (net (code "88") (name "Net-(U3-LED2)") (class "Default")
      (node (ref "R16") (pin "1") (pinfunction "1_1") (pintype "passive"))
      (node (ref "U3") (pin "3") (pinfunction "LED2_3") (pintype "bidirectional"))
    )
    (net (code "89") (name "Net-(U3-LED3)") (class "Default")
      (node (ref "R17") (pin "1") (pinfunction "1_1") (pintype "passive"))
      (node (ref "U3") (pin "4") (pinfunction "LED3_4") (pintype "bidirectional"))
    )
    (net (code "90") (name "Net-(U3-LED4)") (class "Default")
      (node (ref "R18") (pin "1") (pinfunction "1_1") (pintype "passive"))
      (node (ref "U3") (pin "5") (pinfunction "LED4_5") (pintype "bidirectional"))
    )
    (net (code "91") (name "Net-(U3-LED5)") (class "Default")
      (node (ref "R19") (pin "1") (pinfunction "1_1") (pintype "passive"))
      (node (ref "U3") (pin "6") (pinfunction "LED5_6") (pintype "bidirectional"))
    )
    (net (code "92") (name "Net-(U3-LED6)") (class "Default")
      (node (ref "R20") (pin "1") (pinfunction "1_1") (pintype "passive"))
      (node (ref "U3") (pin "7") (pinfunction "LED6_7") (pintype "bidirectional"))
    )
    (net (code "93") (name "Net-(U3-LED7)") (class "Default")
      (node (ref "R21") (pin "1") (pinfunction "1_1") (pintype "passive"))
      (node (ref "U3") (pin "8") (pinfunction "LED7_8") (pintype "bidirectional"))
    )
    (net (code "94") (name "Net-(U3-LED8)") (class "Default")
      (node (ref "R22") (pin "1") (pinfunction "1_1") (pintype "passive"))
      (node (ref "U3") (pin "10") (pinfunction "LED8_10") (pintype "bidirectional"))
    )
    (net (code "95") (name "Net-(U3-LED9)") (class "Default")
      (node (ref "R23") (pin "1") (pinfunction "1_1") (pintype "passive"))
      (node (ref "U3") (pin "11") (pinfunction "LED9_11") (pintype "bidirectional"))
    )
    (net (code "96") (name "Net-(U3-LED10)") (class "Default")
      (node (ref "R24") (pin "1") (pinfunction "1_1") (pintype "passive"))
      (node (ref "U3") (pin "12") (pinfunction "LED10_12") (pintype "bidirectional"))
    )
    (net (code "97") (name "Net-(U3-LED11)") (class "Default")
      (node (ref "R25") (pin "1") (pinfunction "1_1") (pintype "passive"))
      (node (ref "U3") (pin "13") (pinfunction "LED11_13") (pintype "bidirectional"))
    )
    (net (code "98") (name "Net-(U3-LED12)") (class "Default")
      (node (ref "R26") (pin "1") (pinfunction "1_1") (pintype "passive"))
      (node (ref "U3") (pin "14") (pinfunction "LED12_14") (pintype "bidirectional"))
    )
    (net (code "99") (name "Net-(U3-LED13)") (class "Default")
      (node (ref "R27") (pin "1") (pinfunction "1_1") (pintype "passive"))
      (node (ref "U3") (pin "15") (pinfunction "LED13_15") (pintype "bidirectional"))
    )
    (net (code "100") (name "Net-(U3-LED14)") (class "Default")
      (node (ref "R28") (pin "1") (pinfunction "1_1") (pintype "passive"))
      (node (ref "U3") (pin "16") (pinfunction "LED14_16") (pintype "bidirectional"))
    )
    (net (code "101") (name "Net-(U3-LED15)") (class "Default")
      (node (ref "R29") (pin "1") (pinfunction "1_1") (pintype "passive"))
      (node (ref "U3") (pin "17") (pinfunction "LED15_17") (pintype "bidirectional"))
    )
    (net (code "102") (name "Net-(U4-LED0)") (class "Default")
      (node (ref "R45") (pin "1") (pinfunction "1_1") (pintype "passive"))
      (node (ref "U4") (pin "1") (pinfunction "LED0_1") (pintype "bidirectional"))
    )
    (net (code "103") (name "Net-(U4-LED1)") (class "Default")
      (node (ref "R44") (pin "1") (pinfunction "1_1") (pintype "passive"))
      (node (ref "U4") (pin "2") (pinfunction "LED1_2") (pintype "bidirectional"))
    )
    (net (code "104") (name "Net-(U4-LED2)") (class "Default")
      (node (ref "R43") (pin "1") (pinfunction "1_1") (pintype "passive"))
      (node (ref "U4") (pin "3") (pinfunction "LED2_3") (pintype "bidirectional"))
    )
    (net (code "105") (name "Net-(U4-LED3)") (class "Default")
      (node (ref "R42") (pin "1") (pinfunction "1_1") (pintype "passive"))
      (node (ref "U4") (pin "4") (pinfunction "LED3_4") (pintype "bidirectional"))
    )
    (net (code "106") (name "Net-(U4-LED4)") (class "Default")
      (node (ref "R41") (pin "1") (pinfunction "1_1") (pintype "passive"))
      (node (ref "U4") (pin "5") (pinfunction "LED4_5") (pintype "bidirectional"))
    )
    (net (code "107") (name "Net-(U4-LED5)") (class "Default")
      (node (ref "R40") (pin "1") (pinfunction "1_1") (pintype "passive"))
      (node (ref "U4") (pin "6") (pinfunction "LED5_6") (pintype "bidirectional"))
    )
    (net (code "108") (name "Net-(U4-LED6)") (class "Default")
      (node (ref "R39") (pin "1") (pinfunction "1_1") (pintype "passive"))
      (node (ref "U4") (pin "7") (pinfunction "LED6_7") (pintype "bidirectional"))
    )
    (net (code "109") (name "Net-(U4-LED7)") (class "Default")
      (node (ref "R38") (pin "1") (pinfunction "1_1") (pintype "passive"))
      (node (ref "U4") (pin "8") (pinfunction "LED7_8") (pintype "bidirectional"))
    )
    (net (code "110") (name "Net-(U4-LED8)") (class "Default")
      (node (ref "R37") (pin "1") (pinfunction "1_1") (pintype "passive"))
      (node (ref "U4") (pin "10") (pinfunction "LED8_10") (pintype "bidirectional"))
    )
    (net (code "111") (name "Net-(U4-LED9)") (class "Default")
      (node (ref "R36") (pin "1") (pinfunction "1_1") (pintype "passive"))
      (node (ref "U4") (pin "11") (pinfunction "LED9_11") (pintype "bidirectional"))
    )
    (net (code "112") (name "Net-(U4-LED10)") (class "Default")
      (node (ref "R35") (pin "1") (pinfunction "1_1") (pintype "passive"))
      (node (ref "U4") (pin "12") (pinfunction "LED10_12") (pintype "bidirectional"))
    )
    (net (code "113") (name "Net-(U4-LED11)") (class "Default")
      (node (ref "R34") (pin "1") (pinfunction "1_1") (pintype "passive"))
      (node (ref "U4") (pin "13") (pinfunction "LED11_13") (pintype "bidirectional"))
    )
    (net (code "114") (name "Net-(U4-LED12)") (class "Default")
      (node (ref "R33") (pin "1") (pinfunction "1_1") (pintype "passive"))
      (node (ref "U4") (pin "14") (pinfunction "LED12_14") (pintype "bidirectional"))
    )
    (net (code "115") (name "Net-(U4-LED13)") (class "Default")
      (node (ref "R32") (pin "1") (pinfunction "1_1") (pintype "passive"))
      (node (ref "U4") (pin "15") (pinfunction "LED13_15") (pintype "bidirectional"))
    )
    (net (code "116") (name "Net-(U4-LED14)") (class "Default")
      (node (ref "R31") (pin "1") (pinfunction "1_1") (pintype "passive"))
      (node (ref "U4") (pin "16") (pinfunction "LED14_16") (pintype "bidirectional"))
    )
    (net (code "117") (name "Net-(U4-LED15)") (class "Default")
      (node (ref "R30") (pin "1") (pinfunction "1_1") (pintype "passive"))
      (node (ref "U4") (pin "17") (pinfunction "LED15_17") (pintype "bidirectional"))
    )
    (net (code "118") (name "Net-(U5-REGOUT)") (class "Default")
      (node (ref "C15") (pin "2") (pinfunction "2_2") (pintype "passive"))
      (node (ref "U5") (pin "10") (pinfunction "REGOUT_10") (pintype "bidirectional"))
    )
    (net (code "119") (name "Net-(U6-LNA{slash}2)") (class "Default")
      (node (ref "C18") (pin "2") (pinfunction "2_2") (pintype "passive"))
      (node (ref "L4") (pin "1") (pinfunction "1_1") (pintype "passive"))
      (node (ref "U6") (pin "2") (pinfunction "LNA/2_2") (pintype "bidirectional"))
    )
    (net (code "120") (name "Net-(U6-MTCK{slash}12)") (class "Default")
      (node (ref "R48") (pin "2") (pinfunction "2_2") (pintype "passive"))
      (node (ref "U6") (pin "12") (pinfunction "MTCK/12_12") (pintype "bidirectional"))
    )
    (net (code "121") (name "Net-(U6-MTDO{slash}13)") (class "Default")
      (node (ref "R49") (pin "2") (pinfunction "2_2") (pintype "passive"))
      (node (ref "U6") (pin "13") (pinfunction "MTDO/13_13") (pintype "bidirectional"))
    )
    (net (code "122") (name "Net-(U6-RES12K{slash}31)") (class "Default")
      (node (ref "R47") (pin "1") (pinfunction "1_1") (pintype "passive"))
      (node (ref "U6") (pin "31") (pinfunction "RES12K/31_31") (pintype "bidirectional"))
    )
    (net (code "123") (name "Net-(U6-SD_CLK{slash}21)") (class "Default")
      (node (ref "R50") (pin "2") (pinfunction "2_2") (pintype "passive"))
      (node (ref "U6") (pin "21") (pinfunction "SD_CLK/21_21") (pintype "bidirectional"))
    )
    (net (code "124") (name "Net-(U6-XTAL_IN{slash}28)") (class "Default")
      (node (ref "C23") (pin "1") (pinfunction "1_1") (pintype "passive"))
      (node (ref "U6") (pin "28") (pinfunction "XTAL_IN/28_28") (pintype "bidirectional"))
      (node (ref "Y3") (pin "3") (pinfunction "2_3") (pintype "passive"))
    )
    (net (code "125") (name "Net-(U6-XTAL_OUT{slash}27)") (class "Default")
      (node (ref "C24") (pin "1") (pinfunction "1_1") (pintype "passive"))
      (node (ref "U6") (pin "27") (pinfunction "XTAL_OUT/27_27") (pintype "bidirectional"))
      (node (ref "Y3") (pin "1") (pinfunction "1_1") (pintype "passive"))
    )
    (net (code "126") (name "Net-(U8-ANT1{slash}12)") (class "Default")
      (node (ref "L5") (pin "2") (pinfunction "2_2") (pintype "passive"))
      (node (ref "L6") (pin "1") (pinfunction "1_1") (pintype "passive"))
      (node (ref "U8") (pin "12") (pinfunction "ANT1/12_12") (pintype "bidirectional"))
    )
    (net (code "127") (name "Net-(U8-ANT2{slash}13)") (class "Default")
      (node (ref "L5") (pin "1") (pinfunction "1_1") (pintype "passive"))
      (node (ref "L7") (pin "1") (pinfunction "1_1") (pintype "passive"))
      (node (ref "U8") (pin "13") (pinfunction "ANT2/13_13") (pintype "bidirectional"))
    )
    (net (code "128") (name "Net-(U8-DVDD{slash}19)") (class "Default")
      (node (ref "C28") (pin "2") (pinfunction "2_2") (pintype "passive"))
      (node (ref "U8") (pin "19") (pinfunction "DVDD/19_19") (pintype "bidirectional"))
    )
    (net (code "129") (name "Net-(U8-IREF{slash}16)") (class "Default")
      (node (ref "R52") (pin "1") (pinfunction "1_1") (pintype "passive"))
      (node (ref "U8") (pin "16") (pinfunction "IREF/16_16") (pintype "bidirectional"))
    )
    (net (code "130") (name "Net-(U8-VDD_PA{slash}11)") (class "Default")
      (node (ref "C31") (pin "1") (pinfunction "1_1") (pintype "passive"))
      (node (ref "C32") (pin "1") (pinfunction "1_1") (pintype "passive"))
      (node (ref "L6") (pin "2") (pinfunction "2_2") (pintype "passive"))
      (node (ref "U8") (pin "11") (pinfunction "VDD_PA/11_11") (pintype "bidirectional"))
    )
    (net (code "131") (name "Net-(U8-XC1{slash}10)") (class "Default")
      (node (ref "C30") (pin "1") (pinfunction "1_1") (pintype "passive"))
      (node (ref "R51") (pin "2") (pinfunction "2_2") (pintype "passive"))
      (node (ref "U8") (pin "10") (pinfunction "XC1/10_10") (pintype "bidirectional"))
      (node (ref "Y4") (pin "3") (pinfunction "2_3") (pintype "passive"))
    )
    (net (code "132") (name "Net-(U8-XC2{slash}9)") (class "Default")
      (node (ref "C29") (pin "1") (pinfunction "1_1") (pintype "passive"))
      (node (ref "R51") (pin "1") (pinfunction "1_1") (pintype "passive"))
      (node (ref "U8") (pin "9") (pinfunction "XC2/9_9") (pintype "bidirectional"))
      (node (ref "Y4") (pin "1") (pinfunction "1_1") (pintype "passive"))
    )
    (net (code "133") (name "SCK") (class "Default")
      (node (ref "TP54") (pin "TP") (pinfunction "TP_TP") (pintype "input"))
      (node (ref "U1") (pin "58") (pinfunction "PTD1/SPI0_SCK_58") (pintype "bidirectional"))
      (node (ref "U8") (pin "3") (pinfunction "SCK/3_3") (pintype "bidirectional"))
    )
    (net (code "134") (name "SCL") (class "Default")
      (node (ref "R8") (pin "2") (pinfunction "2_2") (pintype "passive"))
      (node (ref "TP38") (pin "TP") (pinfunction "TP_TP") (pintype "input"))
      (node (ref "U1") (pin "37") (pinfunction "PTB2/I2C0_SCL_37") (pintype "bidirectional"))
      (node (ref "U3") (pin "19") (pinfunction "SCL_19") (pintype "bidirectional"))
      (node (ref "U4") (pin "19") (pinfunction "SCL_19") (pintype "bidirectional"))
      (node (ref "U5") (pin "23") (pinfunction "SCLK_23") (pintype "bidirectional"))
    )
    (net (code "135") (name "SDA") (class "Default")
      (node (ref "R7") (pin "2") (pinfunction "2_2") (pintype "passive"))
      (node (ref "TP37") (pin "TP") (pinfunction "TP_TP") (pintype "input"))
      (node (ref "U1") (pin "38") (pinfunction "PTB3/I2C0_SDA_38") (pintype "bidirectional"))
      (node (ref "U3") (pin "20") (pinfunction "SDA_20") (pintype "bidirectional"))
      (node (ref "U4") (pin "20") (pinfunction "SDA_20") (pintype "bidirectional"))
      (node (ref "U5") (pin "24") (pinfunction "SDA/MOSI_24") (pintype "bidirectional"))
    )
    (net (code "136") (name "U0RX") (class "Default")
      (node (ref "TP50") (pin "TP") (pinfunction "TP_TP") (pintype "input"))
      (node (ref "U1") (pin "40") (pinfunction "PTB17/UART0_TX_40") (pintype "bidirectional"))
      (node (ref "U6") (pin "25") (pinfunction "U0RXD/25_25") (pintype "bidirectional"))
    )
    (net (code "137") (name "U0TX") (class "Default")
      (node (ref "TP48") (pin "TP") (pinfunction "TP_TP") (pintype "input"))
      (node (ref "U1") (pin "39") (pinfunction "PTB16/UART0_RX_39") (pintype "bidirectional"))
      (node (ref "U6") (pin "26") (pinfunction "U0TXD/26_26") (pintype "bidirectional"))
    )
    (net (code "138") (name "V_IN") (class "Default")
      (node (ref "C9") (pin "1") (pinfunction "1_1") (pintype "passive"))
      (node (ref "L2") (pin "2") (pinfunction "2_2") (pintype "passive"))
      (node (ref "R9") (pin "2") (pinfunction "2_2") (pintype "passive"))
      (node (ref "S1") (pin "3") (pinfunction "S_3") (pintype "passive"))
      (node (ref "U2") (pin "5") (pinfunction "VIN_5") (pintype "power_in"))
      (node (ref "U2") (pin "6") (pinfunction "EN_6") (pintype "input"))
      (node (ref "U2") (pin "8") (pinfunction "PS_8") (pintype "input"))
    )
    (net (code "139") (name "WIFI_RESET") (class "Default")
      (node (ref "R46") (pin "1") (pinfunction "1_1") (pintype "passive"))
      (node (ref "TP45") (pin "TP") (pinfunction "TP_TP") (pintype "input"))
      (node (ref "U1") (pin "43") (pinfunction "PTC0/ADC0_SE14_43") (pintype "bidirectional"))
      (node (ref "U6") (pin "32") (pinfunction "EXT_RSTB/32_32") (pintype "bidirectional"))
    )
    (net (code "140") (name "WP#") (class "Default")
      (node (ref "U6") (pin "19") (pinfunction "SD_DATA_3/19_19") (pintype "bidirectional"))
      (node (ref "U7") (pin "3") (pinfunction "WP#_3") (pintype "bidirectional"))
    )
    (net (code "141") (name "XPD_DCDC") (class "Default")
      (node (ref "TP44") (pin "TP") (pinfunction "TP_TP") (pintype "input"))
      (node (ref "U1") (pin "46") (pinfunction "PTC3/CMP1_IN1_46") (pintype "bidirectional"))
      (node (ref "U6") (pin "8") (pinfunction "XPD_DCDC/8_8") (pintype "bidirectional"))
    )
    (net (code "142") (name "unconnected-(DS6-R-Pad2)") (class "Default")
      (node (ref "DS6") (pin "2") (pinfunction "R_2") (pintype "bidirectional"))
    )
    (net (code "143") (name "unconnected-(DS9-R-Pad2)") (class "Default")
      (node (ref "DS9") (pin "2") (pinfunction "R_2") (pintype "bidirectional"))
    )
    (net (code "144") (name "unconnected-(DS10-R-Pad2)") (class "Default")
      (node (ref "DS10") (pin "2") (pinfunction "R_2") (pintype "bidirectional"))
    )
    (net (code "145") (name "unconnected-(DS13-R-Pad2)") (class "Default")
      (node (ref "DS13") (pin "2") (pinfunction "R_2") (pintype "bidirectional"))
    )
    (net (code "146") (name "unconnected-(S1-O-Pad1)") (class "Default")
      (node (ref "S1") (pin "1") (pinfunction "O_1") (pintype "passive"))
    )
    (net (code "147") (name "unconnected-(U1-ADC0_DM0-Pad10)") (class "Default")
      (node (ref "U1") (pin "10") (pinfunction "ADC0_DM0_10") (pintype "bidirectional"))
    )
    (net (code "148") (name "unconnected-(U1-ADC0_DM3-Pad12)") (class "Default")
      (node (ref "U1") (pin "12") (pinfunction "ADC0_DM3_12") (pintype "bidirectional"))
    )
    (net (code "149") (name "unconnected-(U1-ADC0_DP0-Pad9)") (class "Default")
      (node (ref "U1") (pin "9") (pinfunction "ADC0_DP0_9") (pintype "bidirectional"))
    )
    (net (code "150") (name "unconnected-(U1-ADC0_DP3-Pad11)") (class "Default")
      (node (ref "U1") (pin "11") (pinfunction "ADC0_DP3_11") (pintype "bidirectional"))
    )
    (net (code "151") (name "unconnected-(U1-DAC0-Pad18)") (class "Default")
      (node (ref "U1") (pin "18") (pinfunction "DAC0_18") (pintype "bidirectional"))
    )
    (net (code "152") (name "unconnected-(U1-USB0_DM-Pad6)") (class "Default")
      (node (ref "U1") (pin "6") (pinfunction "USB0_DM_6") (pintype "bidirectional"))
    )
    (net (code "153") (name "unconnected-(U1-USB0_DP-Pad5)") (class "Default")
      (node (ref "U1") (pin "5") (pinfunction "USB0_DP_5") (pintype "bidirectional"))
    )
    (net (code "154") (name "unconnected-(U5-AUX_CL-Pad7)") (class "Default")
      (node (ref "U5") (pin "7") (pinfunction "AUX_CL_7") (pintype "bidirectional"))
    )
    (net (code "155") (name "unconnected-(U5-AUX_DA-Pad21)") (class "Default")
      (node (ref "U5") (pin "21") (pinfunction "AUX_DA_21") (pintype "bidirectional"))
    )
    (net (code "156") (name "unconnected-(U6-GPIO4{slash}16-Pad16)") (class "Default")
      (node (ref "U6") (pin "16") (pinfunction "GPIO4/16_16") (pintype "bidirectional"))
    )
    (net (code "157") (name "unconnected-(U6-GPIO5{slash}24-Pad24)") (class "Default")
      (node (ref "U6") (pin "24") (pinfunction "GPIO5/24_24") (pintype "bidirectional"))
    )
    (net (code "158") (name "unconnected-(U6-MTDI{slash}10-Pad10)") (class "Default")
      (node (ref "U6") (pin "10") (pinfunction "MTDI/10_10") (pintype "bidirectional"))
    )
    (net (code "159") (name "unconnected-(U6-MTMS{slash}9-Pad9)") (class "Default")
      (node (ref "U6") (pin "9") (pinfunction "MTMS/9_9") (pintype "bidirectional"))
    )
    (net (code "160") (name "unconnected-(U6-TOUT{slash}6-Pad6)") (class "Default")
      (node (ref "U6") (pin "6") (pinfunction "TOUT/6_6") (pintype "bidirectional"))
    )
    (net (code "161") (name "unconnected-(U6-VDD_RTC{slash}5-Pad5)") (class "Default")
      (node (ref "U6") (pin "5") (pinfunction "VDD_RTC/5_5") (pintype "bidirectional"))
    )
    (net (code "162") (name "~{CS}") (class "Default")
      (node (ref "TP42") (pin "TP") (pinfunction "TP_TP") (pintype "input"))
      (node (ref "U1") (pin "49") (pinfunction "PTC4/SPI0_PCS0_49") (pintype "bidirectional"))
      (node (ref "U5") (pin "22") (pinfunction "~{CS}_22") (pintype "bidirectional"))
    )
    (net (code "163") (name "~{RESET0}") (class "Default")
      (node (ref "TP39") (pin "TP") (pinfunction "TP_TP") (pintype "input"))
      (node (ref "U1") (pin "56") (pinfunction "PTC11/ADC1_SE7B_56") (pintype "bidirectional"))
      (node (ref "U3") (pin "18") (pinfunction "~{RESET}_18") (pintype "bidirectional"))
    )
    (net (code "164") (name "~{RESET1}") (class "Default")
      (node (ref "TP40") (pin "TP") (pinfunction "TP_TP") (pintype "input"))
      (node (ref "U1") (pin "27") (pinfunction "PTA5_27") (pintype "bidirectional"))
      (node (ref "U4") (pin "18") (pinfunction "~{RESET}_18") (pintype "bidirectional"))
    )
  )
)
